# PitchshiftDelay-Control-v1_2.net
KiCad netlist of a schematic drawn in EAGLE
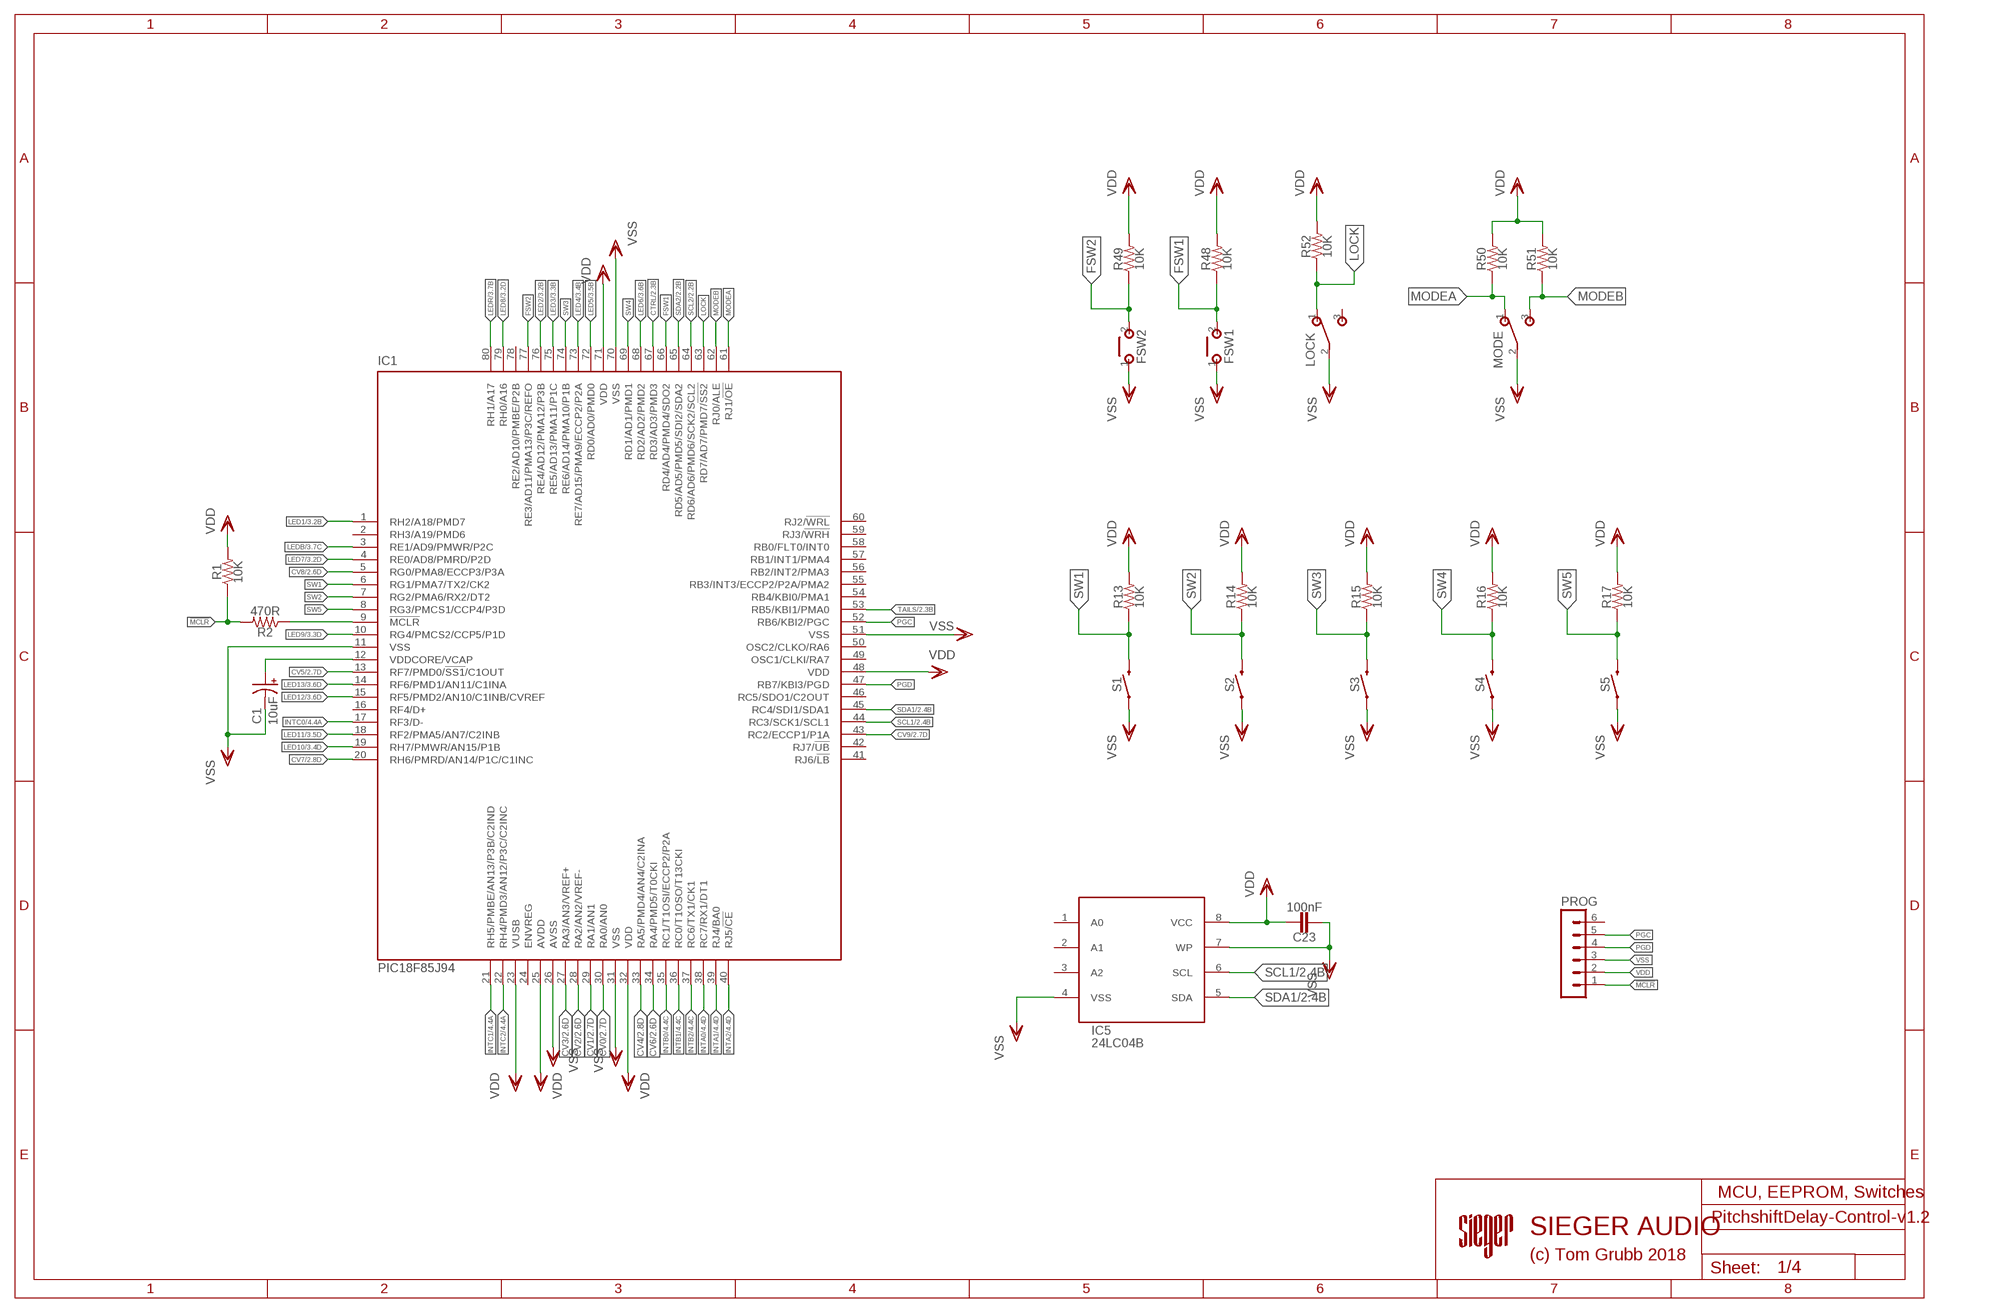
[diagram p0: schematic, sheet 1]
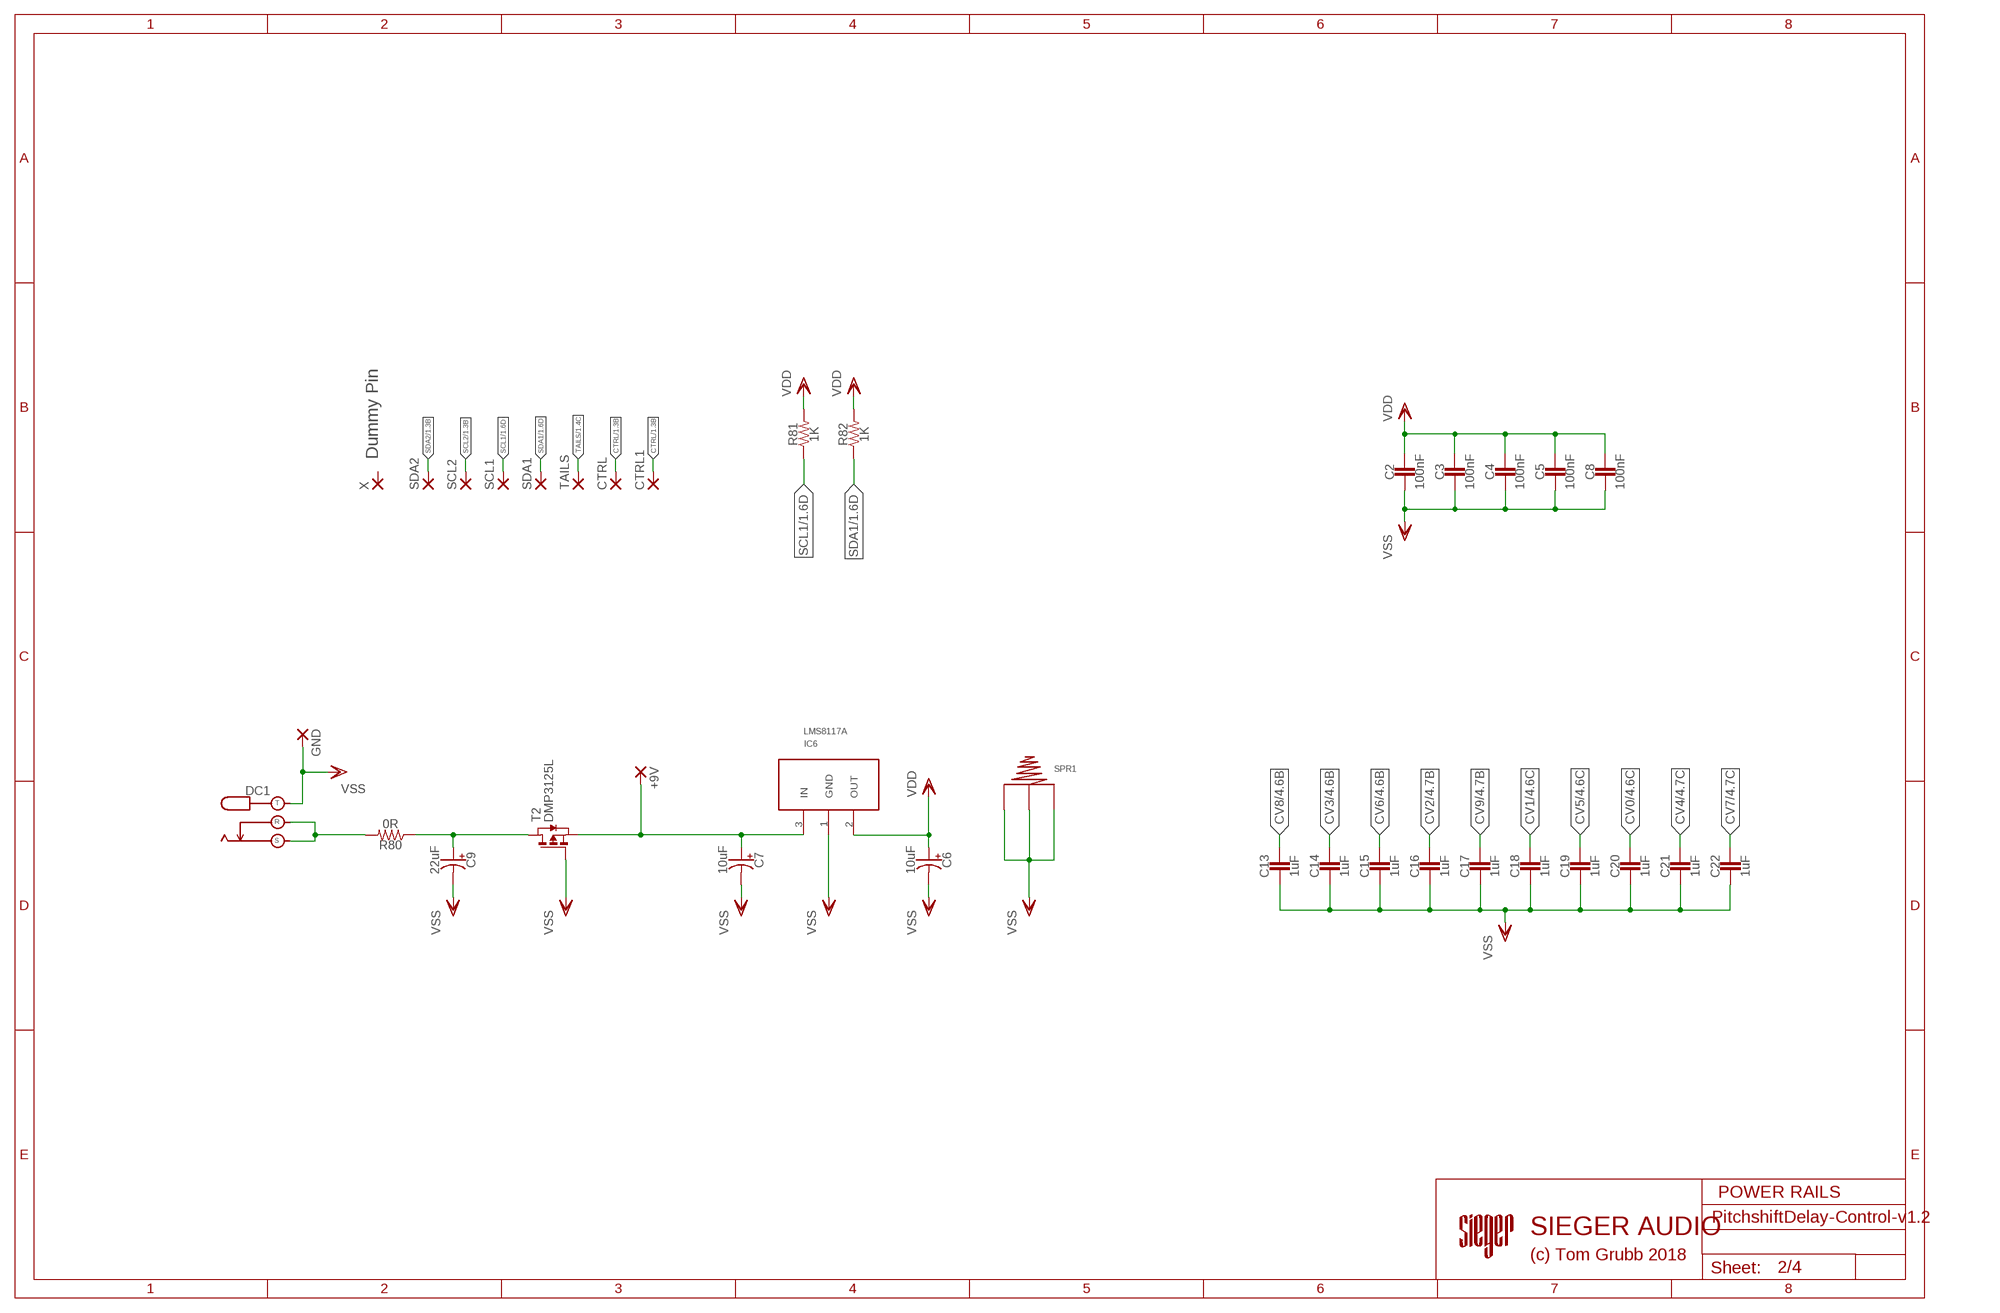
[diagram p1: schematic, sheet 2]
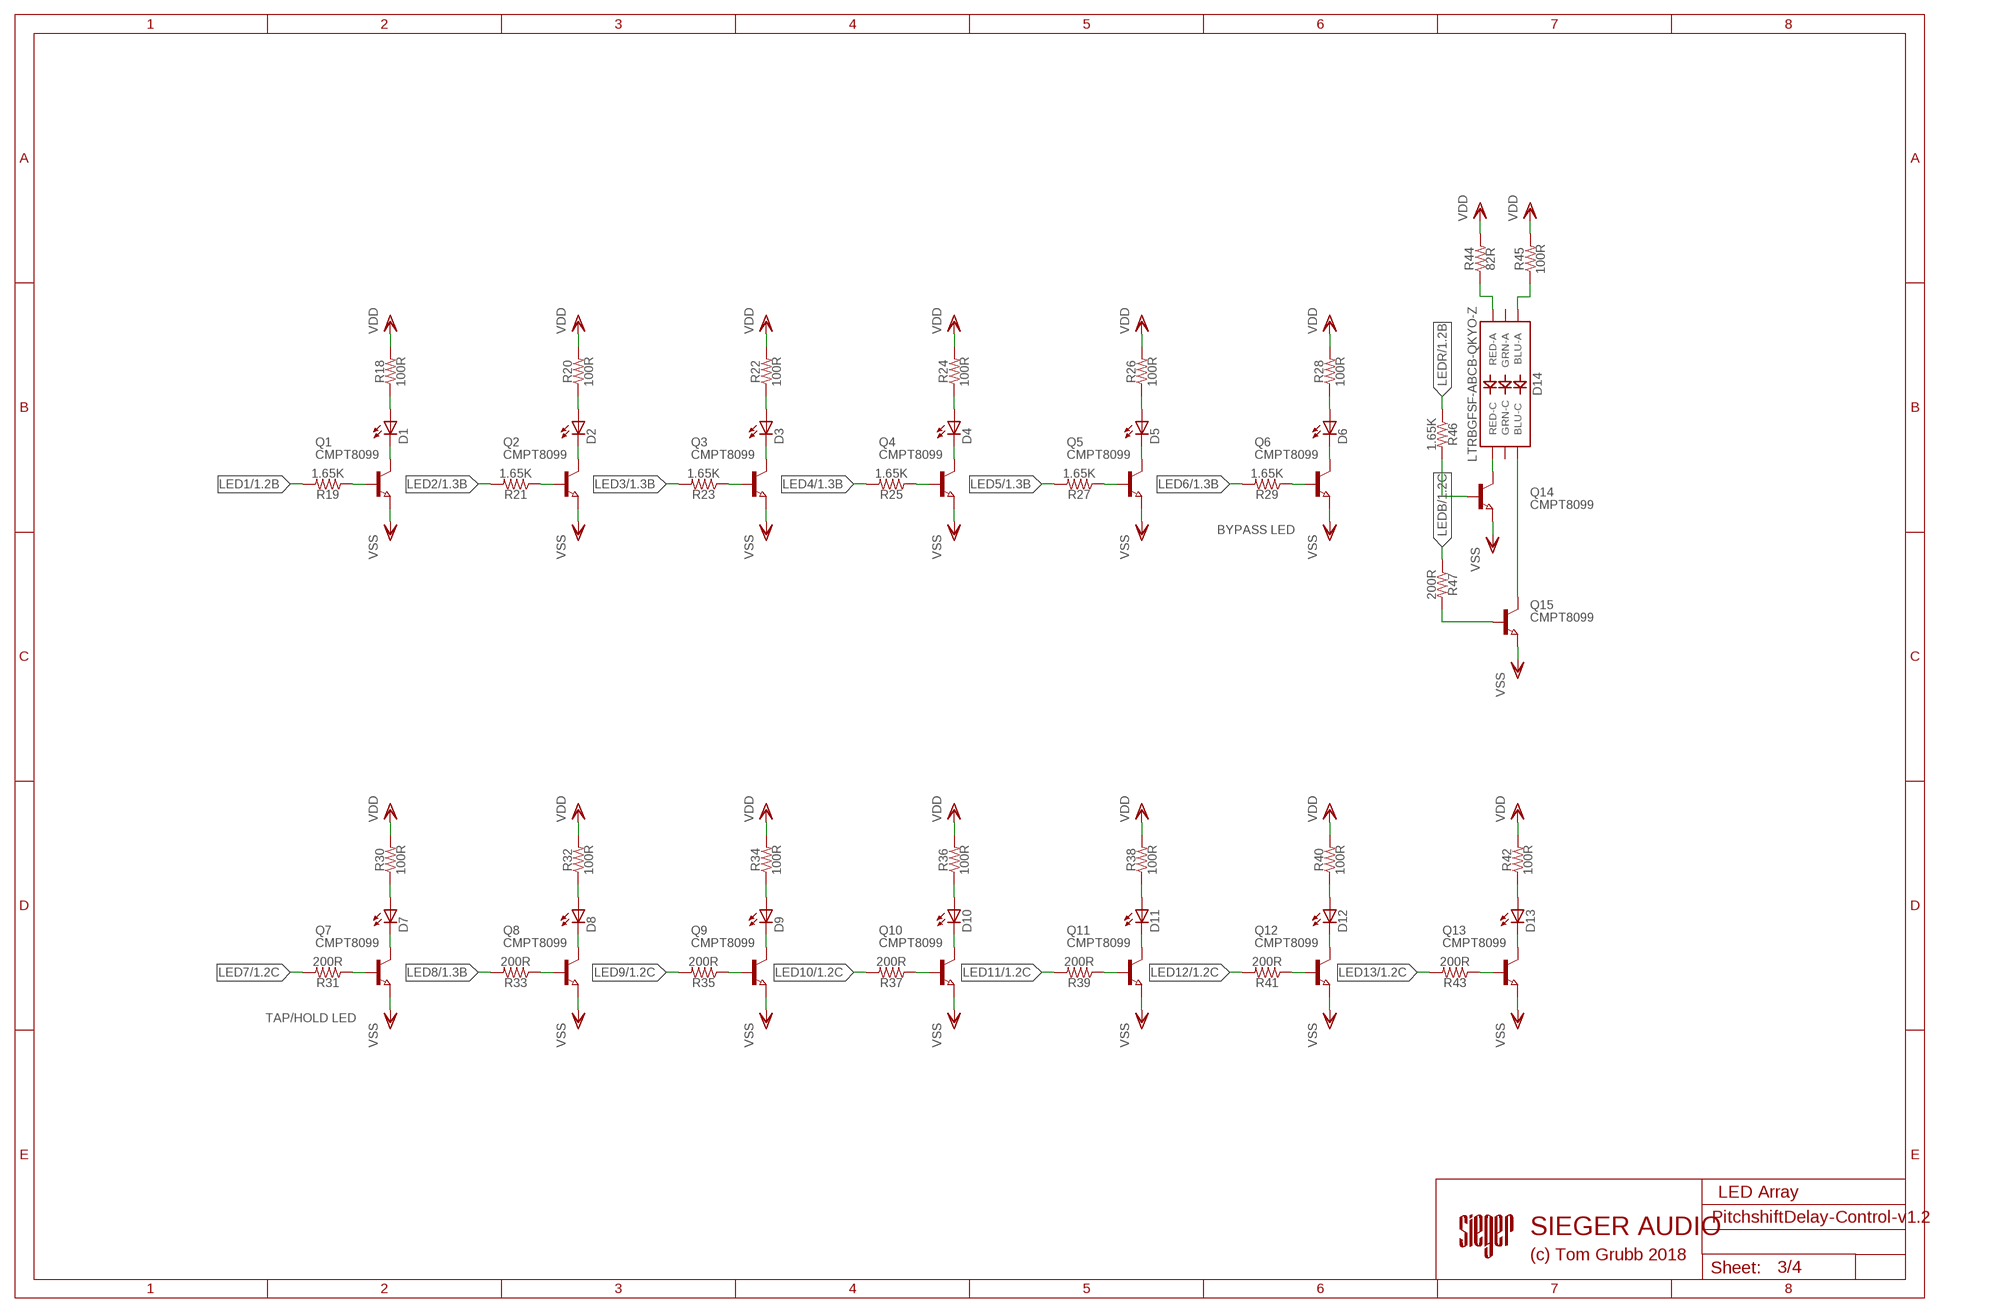
[diagram p2: schematic, sheet 3]
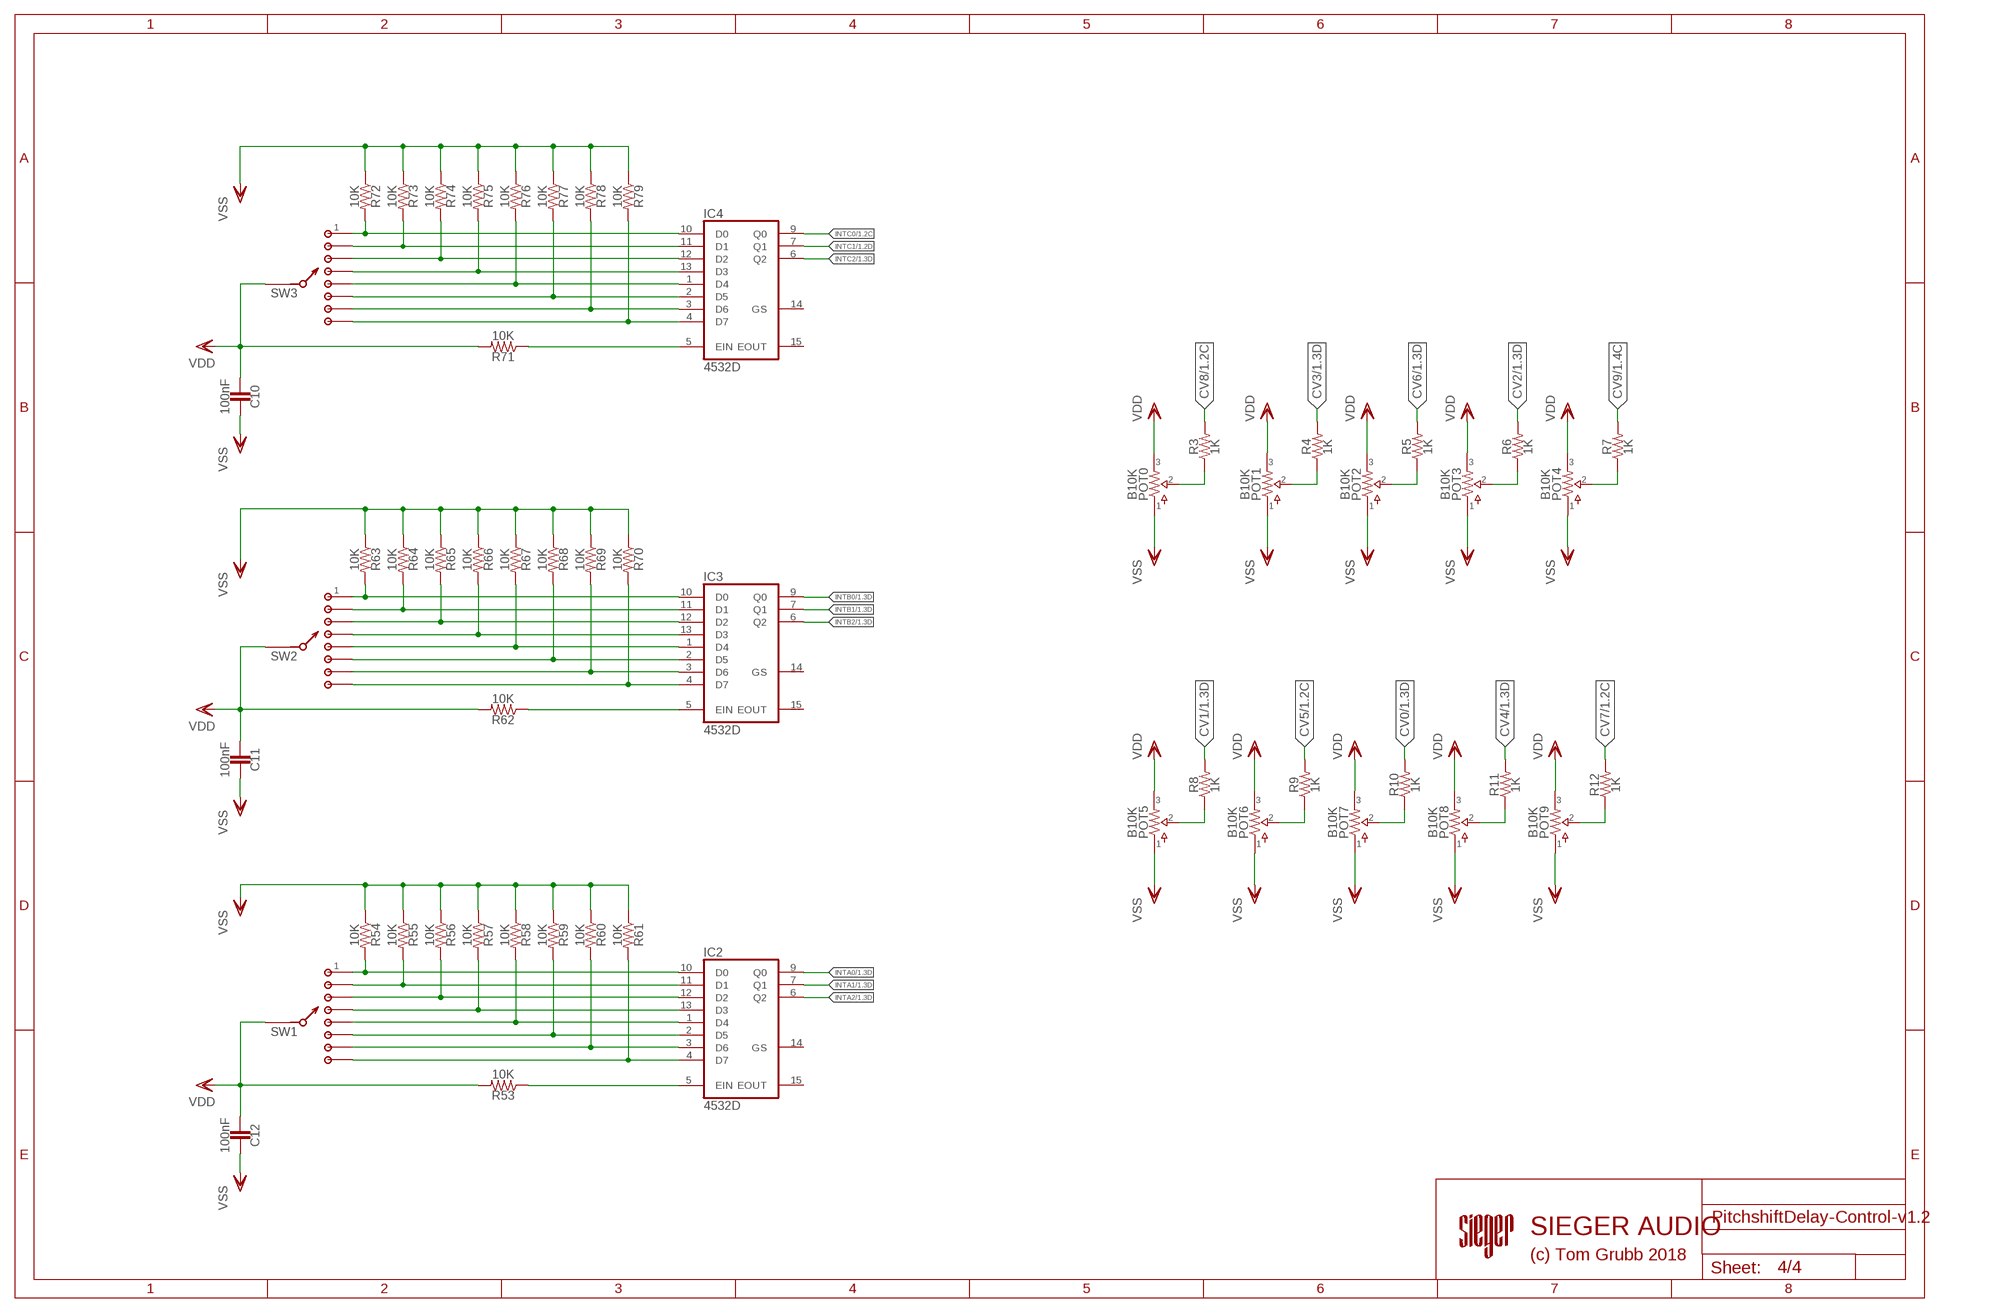
[diagram p3: schematic, sheet 4]

(export (version "E")
  (design (tool "Eeschema 10.0.6"))
  (components
    (comp (ref "C10")
      (value "100nF")
      (footprint "eagle-import:050X030_025")
      (libsource (lib "eagle-import") (part "CER/FILM1"))
    )
    (comp (ref "C11")
      (value "100nF")
      (footprint "eagle-import:050X030_025")
      (libsource (lib "eagle-import") (part "CER/FILM1"))
    )
    (comp (ref "C12")
      (value "100nF")
      (footprint "eagle-import:050X030_025")
      (libsource (lib "eagle-import") (part "CER/FILM1"))
    )
    (comp (ref "IC2")
      (value "4532D")
      (footprint "eagle-import:SO16")
      (libsource (lib "eagle-import") (part "4532D"))
    )
    (comp (ref "IC3")
      (value "4532D")
      (footprint "eagle-import:SO16")
      (libsource (lib "eagle-import") (part "4532D"))
    )
    (comp (ref "IC4")
      (value "4532D")
      (footprint "eagle-import:SO16")
      (libsource (lib "eagle-import") (part "4532D"))
    )
    (comp (ref "POT0")
      (value "B10K")
      (footprint "eagle-import:9MM_W_MOUNTS-2MMHOLES")
      (libsource (lib "eagle-import") (part "POTS9MM_MOUNTED_2MMH"))
    )
    (comp (ref "POT1")
      (value "B10K")
      (footprint "eagle-import:9MM_W_MOUNTS-2MMHOLES")
      (libsource (lib "eagle-import") (part "POTS9MM_MOUNTED_2MMH"))
    )
    (comp (ref "POT2")
      (value "B10K")
      (footprint "eagle-import:9MM_W_MOUNTS-2MMHOLES")
      (libsource (lib "eagle-import") (part "POTS9MM_MOUNTED_2MMH"))
    )
    (comp (ref "POT3")
      (value "B10K")
      (footprint "eagle-import:9MM_W_MOUNTS-2MMHOLES")
      (libsource (lib "eagle-import") (part "POTS9MM_MOUNTED_2MMH"))
    )
    (comp (ref "POT4")
      (value "B10K")
      (footprint "eagle-import:9MM_W_MOUNTS-2MMHOLES")
      (libsource (lib "eagle-import") (part "POTS9MM_MOUNTED_2MMH"))
    )
    (comp (ref "POT5")
      (value "B10K")
      (footprint "eagle-import:9MM_W_MOUNTS-2MMHOLES")
      (libsource (lib "eagle-import") (part "POTS9MM_MOUNTED_2MMH"))
    )
    (comp (ref "POT6")
      (value "B10K")
      (footprint "eagle-import:9MM_W_MOUNTS-2MMHOLES")
      (libsource (lib "eagle-import") (part "POTS9MM_MOUNTED_2MMH"))
    )
    (comp (ref "POT7")
      (value "B10K")
      (footprint "eagle-import:9MM_W_MOUNTS-2MMHOLES")
      (libsource (lib "eagle-import") (part "POTS9MM_MOUNTED_2MMH"))
    )
    (comp (ref "POT8")
      (value "B10K")
      (footprint "eagle-import:9MM_W_MOUNTS-2MMHOLES")
      (libsource (lib "eagle-import") (part "POTS9MM_MOUNTED_2MMH"))
    )
    (comp (ref "POT9")
      (value "B10K")
      (footprint "eagle-import:9MM_W_MOUNTS-2MMHOLES")
      (libsource (lib "eagle-import") (part "POTS9MM_MOUNTED_2MMH"))
    )
    (comp (ref "R3")
      (value "1K")
      (footprint "eagle-import:RESISTOR_C0805")
      (libsource (lib "eagle-import") (part "RESISTOR0805"))
    )
    (comp (ref "R4")
      (value "1K")
      (footprint "eagle-import:RESISTOR_C0805")
      (libsource (lib "eagle-import") (part "RESISTOR0805"))
    )
    (comp (ref "R5")
      (value "1K")
      (footprint "eagle-import:RESISTOR_C0805")
      (libsource (lib "eagle-import") (part "RESISTOR0805"))
    )
    (comp (ref "R6")
      (value "1K")
      (footprint "eagle-import:RESISTOR_C0805")
      (libsource (lib "eagle-import") (part "RESISTOR0805"))
    )
    (comp (ref "R7")
      (value "1K")
      (footprint "eagle-import:RESISTOR_C0805")
      (libsource (lib "eagle-import") (part "RESISTOR0805"))
    )
    (comp (ref "R8")
      (value "1K")
      (footprint "eagle-import:RESISTOR_C0805")
      (libsource (lib "eagle-import") (part "RESISTOR0805"))
    )
    (comp (ref "R9")
      (value "1K")
      (footprint "eagle-import:RESISTOR_C0805")
      (libsource (lib "eagle-import") (part "RESISTOR0805"))
    )
    (comp (ref "R10")
      (value "1K")
      (footprint "eagle-import:RESISTOR_C0805")
      (libsource (lib "eagle-import") (part "RESISTOR0805"))
    )
    (comp (ref "R11")
      (value "1K")
      (footprint "eagle-import:RESISTOR_C0805")
      (libsource (lib "eagle-import") (part "RESISTOR0805"))
    )
    (comp (ref "R12")
      (value "1K")
      (footprint "eagle-import:RESISTOR_C0805")
      (libsource (lib "eagle-import") (part "RESISTOR0805"))
    )
    (comp (ref "R53")
      (value "10K")
      (footprint "eagle-import:RESISTOR_C0805")
      (fields (field (name "SPICEPREFIX") "R"))
      (libsource (lib "eagle-import") (part "RESISTOR0805"))
    )
    (comp (ref "R54")
      (value "10K")
      (footprint "eagle-import:RESISTOR_C0805")
      (fields (field (name "SPICEPREFIX") "R"))
      (libsource (lib "eagle-import") (part "RESISTOR0805"))
    )
    (comp (ref "R55")
      (value "10K")
      (footprint "eagle-import:RESISTOR_C0805")
      (fields (field (name "SPICEPREFIX") "R"))
      (libsource (lib "eagle-import") (part "RESISTOR0805"))
    )
    (comp (ref "R56")
      (value "10K")
      (footprint "eagle-import:RESISTOR_C0805")
      (fields (field (name "SPICEPREFIX") "R"))
      (libsource (lib "eagle-import") (part "RESISTOR0805"))
    )
    (comp (ref "R57")
      (value "10K")
      (footprint "eagle-import:RESISTOR_C0805")
      (fields (field (name "SPICEPREFIX") "R"))
      (libsource (lib "eagle-import") (part "RESISTOR0805"))
    )
    (comp (ref "R58")
      (value "10K")
      (footprint "eagle-import:RESISTOR_C0805")
      (fields (field (name "SPICEPREFIX") "R"))
      (libsource (lib "eagle-import") (part "RESISTOR0805"))
    )
    (comp (ref "R59")
      (value "10K")
      (footprint "eagle-import:RESISTOR_C0805")
      (fields (field (name "SPICEPREFIX") "R"))
      (libsource (lib "eagle-import") (part "RESISTOR0805"))
    )
    (comp (ref "R60")
      (value "10K")
      (footprint "eagle-import:RESISTOR_C0805")
      (fields (field (name "SPICEPREFIX") "R"))
      (libsource (lib "eagle-import") (part "RESISTOR0805"))
    )
    (comp (ref "R61")
      (value "10K")
      (footprint "eagle-import:RESISTOR_C0805")
      (fields (field (name "SPICEPREFIX") "R"))
      (libsource (lib "eagle-import") (part "RESISTOR0805"))
    )
    (comp (ref "R62")
      (value "10K")
      (footprint "eagle-import:RESISTOR_C0805")
      (fields (field (name "SPICEPREFIX") "R"))
      (libsource (lib "eagle-import") (part "RESISTOR0805"))
    )
    (comp (ref "R63")
      (value "10K")
      (footprint "eagle-import:RESISTOR_C0805")
      (fields (field (name "SPICEPREFIX") "R"))
      (libsource (lib "eagle-import") (part "RESISTOR0805"))
    )
    (comp (ref "R64")
      (value "10K")
      (footprint "eagle-import:RESISTOR_C0805")
      (fields (field (name "SPICEPREFIX") "R"))
      (libsource (lib "eagle-import") (part "RESISTOR0805"))
    )
    (comp (ref "R65")
      (value "10K")
      (footprint "eagle-import:RESISTOR_C0805")
      (fields (field (name "SPICEPREFIX") "R"))
      (libsource (lib "eagle-import") (part "RESISTOR0805"))
    )
    (comp (ref "R66")
      (value "10K")
      (footprint "eagle-import:RESISTOR_C0805")
      (fields (field (name "SPICEPREFIX") "R"))
      (libsource (lib "eagle-import") (part "RESISTOR0805"))
    )
    (comp (ref "R67")
      (value "10K")
      (footprint "eagle-import:RESISTOR_C0805")
      (fields (field (name "SPICEPREFIX") "R"))
      (libsource (lib "eagle-import") (part "RESISTOR0805"))
    )
    (comp (ref "R68")
      (value "10K")
      (footprint "eagle-import:RESISTOR_C0805")
      (fields (field (name "SPICEPREFIX") "R"))
      (libsource (lib "eagle-import") (part "RESISTOR0805"))
    )
    (comp (ref "R69")
      (value "10K")
      (footprint "eagle-import:RESISTOR_C0805")
      (fields (field (name "SPICEPREFIX") "R"))
      (libsource (lib "eagle-import") (part "RESISTOR0805"))
    )
    (comp (ref "R70")
      (value "10K")
      (footprint "eagle-import:RESISTOR_C0805")
      (fields (field (name "SPICEPREFIX") "R"))
      (libsource (lib "eagle-import") (part "RESISTOR0805"))
    )
    (comp (ref "R71")
      (value "10K")
      (footprint "eagle-import:RESISTOR_C0805")
      (fields (field (name "SPICEPREFIX") "R"))
      (libsource (lib "eagle-import") (part "RESISTOR0805"))
    )
    (comp (ref "R72")
      (value "10K")
      (footprint "eagle-import:RESISTOR_C0805")
      (fields (field (name "SPICEPREFIX") "R"))
      (libsource (lib "eagle-import") (part "RESISTOR0805"))
    )
    (comp (ref "R73")
      (value "10K")
      (footprint "eagle-import:RESISTOR_C0805")
      (fields (field (name "SPICEPREFIX") "R"))
      (libsource (lib "eagle-import") (part "RESISTOR0805"))
    )
    (comp (ref "R74")
      (value "10K")
      (footprint "eagle-import:RESISTOR_C0805")
      (fields (field (name "SPICEPREFIX") "R"))
      (libsource (lib "eagle-import") (part "RESISTOR0805"))
    )
    (comp (ref "R75")
      (value "10K")
      (footprint "eagle-import:RESISTOR_C0805")
      (fields (field (name "SPICEPREFIX") "R"))
      (libsource (lib "eagle-import") (part "RESISTOR0805"))
    )
    (comp (ref "R76")
      (value "10K")
      (footprint "eagle-import:RESISTOR_C0805")
      (fields (field (name "SPICEPREFIX") "R"))
      (libsource (lib "eagle-import") (part "RESISTOR0805"))
    )
    (comp (ref "R77")
      (value "10K")
      (footprint "eagle-import:RESISTOR_C0805")
      (fields (field (name "SPICEPREFIX") "R"))
      (libsource (lib "eagle-import") (part "RESISTOR0805"))
    )
    (comp (ref "R78")
      (value "10K")
      (footprint "eagle-import:RESISTOR_C0805")
      (fields (field (name "SPICEPREFIX") "R"))
      (libsource (lib "eagle-import") (part "RESISTOR0805"))
    )
    (comp (ref "R79")
      (value "10K")
      (footprint "eagle-import:RESISTOR_C0805")
      (fields (field (name "SPICEPREFIX") "R"))
      (libsource (lib "eagle-import") (part "RESISTOR0805"))
    )
    (comp (ref "SW1")
      (value "1P8T")
      (footprint "eagle-import:SMALLROTARY")
      (libsource (lib "eagle-import") (part "1P8T"))
    )
    (comp (ref "SW2")
      (value "1P8T")
      (footprint "eagle-import:SMALLROTARY")
      (libsource (lib "eagle-import") (part "1P8T"))
    )
    (comp (ref "SW3")
      (value "1P8T")
      (footprint "eagle-import:SMALLROTARY")
      (libsource (lib "eagle-import") (part "1P8T"))
    )
    (comp (ref "+9V")
      (value "2,15/1,0")
      (footprint "eagle-import:2,15_1,0")
      (libsource (lib "eagle-import") (part "2,15/1,0"))
    )
    (comp (ref "C2")
      (value "100nF")
      (footprint "eagle-import:050X030_025")
      (libsource (lib "eagle-import") (part "CER/FILM1"))
    )
    (comp (ref "C3")
      (value "100nF")
      (footprint "eagle-import:050X030_025")
      (libsource (lib "eagle-import") (part "CER/FILM1"))
    )
    (comp (ref "C4")
      (value "100nF")
      (footprint "eagle-import:050X030_025")
      (libsource (lib "eagle-import") (part "CER/FILM1"))
    )
    (comp (ref "C5")
      (value "100nF")
      (footprint "eagle-import:050X030_025")
      (libsource (lib "eagle-import") (part "CER/FILM1"))
    )
    (comp (ref "C6")
      (value "10uF")
      (footprint "eagle-import:050_020_1")
      (libsource (lib "eagle-import") (part "0501"))
    )
    (comp (ref "C7")
      (value "10uF")
      (footprint "eagle-import:050_020_1")
      (libsource (lib "eagle-import") (part "0501"))
    )
    (comp (ref "C8")
      (value "100nF")
      (footprint "eagle-import:050X030_025")
      (libsource (lib "eagle-import") (part "CER/FILM1"))
    )
    (comp (ref "C9")
      (value "22uF")
      (footprint "eagle-import:050_020_1")
      (libsource (lib "eagle-import") (part "0501"))
    )
    (comp (ref "C13")
      (value "1uF")
      (footprint "eagle-import:050X030_025")
      (libsource (lib "eagle-import") (part "CER/FILM1"))
    )
    (comp (ref "C14")
      (value "1uF")
      (footprint "eagle-import:050X030_025")
      (libsource (lib "eagle-import") (part "CER/FILM1"))
    )
    (comp (ref "C15")
      (value "1uF")
      (footprint "eagle-import:050X030_025")
      (libsource (lib "eagle-import") (part "CER/FILM1"))
    )
    (comp (ref "C16")
      (value "1uF")
      (footprint "eagle-import:050X030_025")
      (libsource (lib "eagle-import") (part "CER/FILM1"))
    )
    (comp (ref "C17")
      (value "1uF")
      (footprint "eagle-import:050X030_025")
      (libsource (lib "eagle-import") (part "CER/FILM1"))
    )
    (comp (ref "C18")
      (value "1uF")
      (footprint "eagle-import:050X030_025")
      (libsource (lib "eagle-import") (part "CER/FILM1"))
    )
    (comp (ref "C19")
      (value "1uF")
      (footprint "eagle-import:050X030_025")
      (libsource (lib "eagle-import") (part "CER/FILM1"))
    )
    (comp (ref "C20")
      (value "1uF")
      (footprint "eagle-import:050X030_025")
      (libsource (lib "eagle-import") (part "CER/FILM1"))
    )
    (comp (ref "C21")
      (value "1uF")
      (footprint "eagle-import:050X030_025")
      (libsource (lib "eagle-import") (part "CER/FILM1"))
    )
    (comp (ref "C22")
      (value "1uF")
      (footprint "eagle-import:050X030_025")
      (libsource (lib "eagle-import") (part "CER/FILM1"))
    )
    (comp (ref "CTRL")
      (value "2,15/1,0")
      (footprint "eagle-import:2,15_1,0")
      (libsource (lib "eagle-import") (part "2,15/1,0"))
    )
    (comp (ref "CTRL1")
      (value "2,15/1,0")
      (footprint "eagle-import:2,15_1,0")
      (libsource (lib "eagle-import") (part "2,15/1,0"))
    )
    (comp (ref "DC1")
      (value "DC_KOBICONN")
      (footprint "eagle-import:DC_KOBICONN")
      (libsource (lib "eagle-import") (part "DC_KOBICONN"))
    )
    (comp (ref "GND")
      (value "2,15/1,0")
      (footprint "eagle-import:2,15_1,0")
      (libsource (lib "eagle-import") (part "2,15/1,0"))
    )
    (comp (ref "IC6")
      (value "LMS8117A")
      (footprint "eagle-import:SOT223")
      (libsource (lib "eagle-import") (part "LMS8117A"))
    )
    (comp (ref "R80")
      (value "0R")
      (footprint "eagle-import:RESISTOR_C0805")
      (libsource (lib "eagle-import") (part "RESISTOR0805"))
    )
    (comp (ref "R81")
      (value "1K")
      (footprint "eagle-import:RESISTOR_C0805")
      (libsource (lib "eagle-import") (part "RESISTOR0805"))
    )
    (comp (ref "R82")
      (value "1K")
      (footprint "eagle-import:RESISTOR_C0805")
      (libsource (lib "eagle-import") (part "RESISTOR0805"))
    )
    (comp (ref "SCL1")
      (value "2,15/1,0")
      (footprint "eagle-import:2,15_1,0")
      (libsource (lib "eagle-import") (part "2,15/1,0"))
    )
    (comp (ref "SCL2")
      (value "2,15/1,0")
      (footprint "eagle-import:2,15_1,0")
      (libsource (lib "eagle-import") (part "2,15/1,0"))
    )
    (comp (ref "SDA1")
      (value "2,15/1,0")
      (footprint "eagle-import:2,15_1,0")
      (libsource (lib "eagle-import") (part "2,15/1,0"))
    )
    (comp (ref "SDA2")
      (value "2,15/1,0")
      (footprint "eagle-import:2,15_1,0")
      (libsource (lib "eagle-import") (part "2,15/1,0"))
    )
    (comp (ref "SPR1")
      (value "534-628")
      (footprint "eagle-import:'A'SIZE-PC-SPRING")
      (libsource (lib "eagle-import") (part "SPRING"))
    )
    (comp (ref "T2")
      (value "DMP3125L")
      (footprint "eagle-import:SOT-23")
      (libsource (lib "eagle-import") (part "PMOSSOT23"))
    )
    (comp (ref "TAILS")
      (value "2,15/1,0")
      (footprint "eagle-import:2,15_1,0")
      (libsource (lib "eagle-import") (part "2,15/1,0"))
    )
    (comp (ref "X")
      (value "2,15/1,0")
      (footprint "eagle-import:2,15_1,0")
      (libsource (lib "eagle-import") (part "2,15/1,0"))
    )
    (comp (ref "D1")
      (value "LEDCHIP-LED0805")
      (footprint "eagle-import:CHIP-LED0805")
      (libsource (lib "eagle-import") (part "LEDCHIP-LED0805"))
    )
    (comp (ref "D2")
      (value "LEDCHIP-LED0805")
      (footprint "eagle-import:CHIP-LED0805")
      (libsource (lib "eagle-import") (part "LEDCHIP-LED0805"))
    )
    (comp (ref "D3")
      (value "LEDCHIP-LED0805")
      (footprint "eagle-import:CHIP-LED0805")
      (libsource (lib "eagle-import") (part "LEDCHIP-LED0805"))
    )
    (comp (ref "D4")
      (value "LEDCHIP-LED0805")
      (footprint "eagle-import:CHIP-LED0805")
      (libsource (lib "eagle-import") (part "LEDCHIP-LED0805"))
    )
    (comp (ref "D5")
      (value "LEDCHIP-LED0805")
      (footprint "eagle-import:CHIP-LED0805")
      (libsource (lib "eagle-import") (part "LEDCHIP-LED0805"))
    )
    (comp (ref "D6")
      (value "LEDCHIPLED_1206")
      (footprint "eagle-import:CHIPLED_1206")
      (libsource (lib "eagle-import") (part "LEDCHIPLED_1206"))
    )
    (comp (ref "D7")
      (value "LEDCHIPLED_1206")
      (footprint "eagle-import:CHIPLED_1206")
      (libsource (lib "eagle-import") (part "LEDCHIPLED_1206"))
    )
    (comp (ref "D8")
      (value "LEDCHIP-LED0805")
      (footprint "eagle-import:CHIP-LED0805")
      (libsource (lib "eagle-import") (part "LEDCHIP-LED0805"))
    )
    (comp (ref "D9")
      (value "LEDCHIP-LED0805")
      (footprint "eagle-import:CHIP-LED0805")
      (libsource (lib "eagle-import") (part "LEDCHIP-LED0805"))
    )
    (comp (ref "D10")
      (value "LEDCHIP-LED0805")
      (footprint "eagle-import:CHIP-LED0805")
      (libsource (lib "eagle-import") (part "LEDCHIP-LED0805"))
    )
    (comp (ref "D11")
      (value "LEDCHIP-LED0805")
      (footprint "eagle-import:CHIP-LED0805")
      (libsource (lib "eagle-import") (part "LEDCHIP-LED0805"))
    )
    (comp (ref "D12")
      (value "LEDCHIP-LED0805")
      (footprint "eagle-import:CHIP-LED0805")
      (libsource (lib "eagle-import") (part "LEDCHIP-LED0805"))
    )
    (comp (ref "D13")
      (value "LEDCHIP-LED0805")
      (footprint "eagle-import:CHIP-LED0805")
      (libsource (lib "eagle-import") (part "LEDCHIP-LED0805"))
    )
    (comp (ref "D14")
      (value "LTRBGFSF-ABCB-QKYO-Z")
      (footprint "eagle-import:PLCC-6-LED")
      (libsource (lib "eagle-import") (part "LED-RGBPLCC-6"))
    )
    (comp (ref "Q1")
      (value "CMPT8099")
      (footprint "eagle-import:SOT23")
      (libsource (lib "eagle-import") (part "NPN-TRANSISTOR_SOT23"))
    )
    (comp (ref "Q2")
      (value "CMPT8099")
      (footprint "eagle-import:SOT23")
      (libsource (lib "eagle-import") (part "NPN-TRANSISTOR_SOT23"))
    )
    (comp (ref "Q3")
      (value "CMPT8099")
      (footprint "eagle-import:SOT23")
      (libsource (lib "eagle-import") (part "NPN-TRANSISTOR_SOT23"))
    )
    (comp (ref "Q4")
      (value "CMPT8099")
      (footprint "eagle-import:SOT23")
      (libsource (lib "eagle-import") (part "NPN-TRANSISTOR_SOT23"))
    )
    (comp (ref "Q5")
      (value "CMPT8099")
      (footprint "eagle-import:SOT23")
      (libsource (lib "eagle-import") (part "NPN-TRANSISTOR_SOT23"))
    )
    (comp (ref "Q6")
      (value "CMPT8099")
      (footprint "eagle-import:SOT23")
      (libsource (lib "eagle-import") (part "NPN-TRANSISTOR_SOT23"))
    )
    (comp (ref "Q7")
      (value "CMPT8099")
      (footprint "eagle-import:SOT23")
      (libsource (lib "eagle-import") (part "NPN-TRANSISTOR_SOT23"))
    )
    (comp (ref "Q8")
      (value "CMPT8099")
      (footprint "eagle-import:SOT23")
      (libsource (lib "eagle-import") (part "NPN-TRANSISTOR_SOT23"))
    )
    (comp (ref "Q9")
      (value "CMPT8099")
      (footprint "eagle-import:SOT23")
      (libsource (lib "eagle-import") (part "NPN-TRANSISTOR_SOT23"))
    )
    (comp (ref "Q10")
      (value "CMPT8099")
      (footprint "eagle-import:SOT23")
      (libsource (lib "eagle-import") (part "NPN-TRANSISTOR_SOT23"))
    )
    (comp (ref "Q11")
      (value "CMPT8099")
      (footprint "eagle-import:SOT23")
      (libsource (lib "eagle-import") (part "NPN-TRANSISTOR_SOT23"))
    )
    (comp (ref "Q12")
      (value "CMPT8099")
      (footprint "eagle-import:SOT23")
      (libsource (lib "eagle-import") (part "NPN-TRANSISTOR_SOT23"))
    )
    (comp (ref "Q13")
      (value "CMPT8099")
      (footprint "eagle-import:SOT23")
      (libsource (lib "eagle-import") (part "NPN-TRANSISTOR_SOT23"))
    )
    (comp (ref "Q14")
      (value "CMPT8099")
      (footprint "eagle-import:SOT23")
      (libsource (lib "eagle-import") (part "NPN-TRANSISTOR_SOT23"))
    )
    (comp (ref "Q15")
      (value "CMPT8099")
      (footprint "eagle-import:SOT23")
      (libsource (lib "eagle-import") (part "NPN-TRANSISTOR_SOT23"))
    )
    (comp (ref "R18")
      (value "100R")
      (footprint "eagle-import:RESISTOR_C0805")
      (libsource (lib "eagle-import") (part "RESISTOR0805"))
    )
    (comp (ref "R19")
      (value "1.65K")
      (footprint "eagle-import:RESISTOR_C0805")
      (libsource (lib "eagle-import") (part "RESISTOR0805"))
    )
    (comp (ref "R20")
      (value "100R")
      (footprint "eagle-import:RESISTOR_C0805")
      (libsource (lib "eagle-import") (part "RESISTOR0805"))
    )
    (comp (ref "R21")
      (value "1.65K")
      (footprint "eagle-import:RESISTOR_C0805")
      (libsource (lib "eagle-import") (part "RESISTOR0805"))
    )
    (comp (ref "R22")
      (value "100R")
      (footprint "eagle-import:RESISTOR_C0805")
      (libsource (lib "eagle-import") (part "RESISTOR0805"))
    )
    (comp (ref "R23")
      (value "1.65K")
      (footprint "eagle-import:RESISTOR_C0805")
      (libsource (lib "eagle-import") (part "RESISTOR0805"))
    )
    (comp (ref "R24")
      (value "100R")
      (footprint "eagle-import:RESISTOR_C0805")
      (libsource (lib "eagle-import") (part "RESISTOR0805"))
    )
    (comp (ref "R25")
      (value "1.65K")
      (footprint "eagle-import:RESISTOR_C0805")
      (libsource (lib "eagle-import") (part "RESISTOR0805"))
    )
    (comp (ref "R26")
      (value "100R")
      (footprint "eagle-import:RESISTOR_C0805")
      (libsource (lib "eagle-import") (part "RESISTOR0805"))
    )
    (comp (ref "R27")
      (value "1.65K")
      (footprint "eagle-import:RESISTOR_C0805")
      (libsource (lib "eagle-import") (part "RESISTOR0805"))
    )
    (comp (ref "R28")
      (value "100R")
      (footprint "eagle-import:RESISTOR_C0805")
      (libsource (lib "eagle-import") (part "RESISTOR0805"))
    )
    (comp (ref "R29")
      (value "1.65K")
      (footprint "eagle-import:RESISTOR_C0805")
      (libsource (lib "eagle-import") (part "RESISTOR0805"))
    )
    (comp (ref "R30")
      (value "100R")
      (footprint "eagle-import:RESISTOR_C0805")
      (libsource (lib "eagle-import") (part "RESISTOR0805"))
    )
    (comp (ref "R31")
      (value "200R")
      (footprint "eagle-import:RESISTOR_C0805")
      (libsource (lib "eagle-import") (part "RESISTOR0805"))
    )
    (comp (ref "R32")
      (value "100R")
      (footprint "eagle-import:RESISTOR_C0805")
      (libsource (lib "eagle-import") (part "RESISTOR0805"))
    )
    (comp (ref "R33")
      (value "200R")
      (footprint "eagle-import:RESISTOR_C0805")
      (libsource (lib "eagle-import") (part "RESISTOR0805"))
    )
    (comp (ref "R34")
      (value "100R")
      (footprint "eagle-import:RESISTOR_C0805")
      (libsource (lib "eagle-import") (part "RESISTOR0805"))
    )
    (comp (ref "R35")
      (value "200R")
      (footprint "eagle-import:RESISTOR_C0805")
      (libsource (lib "eagle-import") (part "RESISTOR0805"))
    )
    (comp (ref "R36")
      (value "100R")
      (footprint "eagle-import:RESISTOR_C0805")
      (libsource (lib "eagle-import") (part "RESISTOR0805"))
    )
    (comp (ref "R37")
      (value "200R")
      (footprint "eagle-import:RESISTOR_C0805")
      (libsource (lib "eagle-import") (part "RESISTOR0805"))
    )
    (comp (ref "R38")
      (value "100R")
      (footprint "eagle-import:RESISTOR_C0805")
      (libsource (lib "eagle-import") (part "RESISTOR0805"))
    )
    (comp (ref "R39")
      (value "200R")
      (footprint "eagle-import:RESISTOR_C0805")
      (libsource (lib "eagle-import") (part "RESISTOR0805"))
    )
    (comp (ref "R40")
      (value "100R")
      (footprint "eagle-import:RESISTOR_C0805")
      (libsource (lib "eagle-import") (part "RESISTOR0805"))
    )
    (comp (ref "R41")
      (value "200R")
      (footprint "eagle-import:RESISTOR_C0805")
      (libsource (lib "eagle-import") (part "RESISTOR0805"))
    )
    (comp (ref "R42")
      (value "100R")
      (footprint "eagle-import:RESISTOR_C0805")
      (libsource (lib "eagle-import") (part "RESISTOR0805"))
    )
    (comp (ref "R43")
      (value "200R")
      (footprint "eagle-import:RESISTOR_C0805")
      (libsource (lib "eagle-import") (part "RESISTOR0805"))
    )
    (comp (ref "R44")
      (value "82R")
      (footprint "eagle-import:RESISTOR_C0805")
      (libsource (lib "eagle-import") (part "RESISTOR0805"))
    )
    (comp (ref "R45")
      (value "100R")
      (footprint "eagle-import:RESISTOR_C0805")
      (libsource (lib "eagle-import") (part "RESISTOR0805"))
    )
    (comp (ref "R46")
      (value "1.65K")
      (footprint "eagle-import:RESISTOR_C0805")
      (libsource (lib "eagle-import") (part "RESISTOR0805"))
    )
    (comp (ref "R47")
      (value "200R")
      (footprint "eagle-import:RESISTOR_C0805")
      (libsource (lib "eagle-import") (part "RESISTOR0805"))
    )
    (comp (ref "C1")
      (value "10uF")
      (footprint "eagle-import:050_020_1")
      (libsource (lib "eagle-import") (part "0501"))
    )
    (comp (ref "C23")
      (value "100nF")
      (footprint "eagle-import:050X030_025")
      (libsource (lib "eagle-import") (part "CER/FILM1"))
    )
    (comp (ref "FSW1")
      (value "MOMENTARY")
      (footprint "eagle-import:SPST")
      (libsource (lib "eagle-import") (part "MOMENTARY"))
    )
    (comp (ref "FSW2")
      (value "MOMENTARY")
      (footprint "eagle-import:SPST")
      (libsource (lib "eagle-import") (part "MOMENTARY"))
    )
    (comp (ref "IC1")
      (value "PIC18F85J94")
      (footprint "eagle-import:TQFP80-12X12")
      (fields (field (name "MPN") "PIC18F85J50-I/PT"))
      (libsource (lib "eagle-import") (part "PIC18F8J505"))
    )
    (comp (ref "IC5")
      (value "24LC04B")
      (footprint "eagle-import:SOIC8")
      (libsource (lib "eagle-import") (part "24LC04B"))
    )
    (comp (ref "LOCK")
      (value "SPDTPIN_MOUNT")
      (footprint "eagle-import:1MS1T1B1C0M2QE")
      (libsource (lib "eagle-import") (part "SPDTPIN_MOUNT"))
    )
    (comp (ref "MODE")
      (value "SPDTPIN_MOUNT")
      (footprint "eagle-import:1MS1T1B1C0M2QE")
      (libsource (lib "eagle-import") (part "SPDTPIN_MOUNT"))
    )
    (comp (ref "PROG")
      (value "MA06-1")
      (footprint "eagle-import:MA06-1")
      (libsource (lib "eagle-import") (part "MA06-1"))
    )
    (comp (ref "R1")
      (value "10K")
      (footprint "eagle-import:RESISTOR_C0805")
      (libsource (lib "eagle-import") (part "RESISTOR0805"))
    )
    (comp (ref "R2")
      (value "470R")
      (footprint "eagle-import:RESISTOR_C0805")
      (libsource (lib "eagle-import") (part "RESISTOR0805"))
    )
    (comp (ref "R13")
      (value "10K")
      (footprint "eagle-import:RESISTOR_C0805")
      (fields (field (name "SPICEPREFIX") "R"))
      (libsource (lib "eagle-import") (part "RESISTOR0805"))
    )
    (comp (ref "R14")
      (value "10K")
      (footprint "eagle-import:RESISTOR_C0805")
      (fields (field (name "SPICEPREFIX") "R"))
      (libsource (lib "eagle-import") (part "RESISTOR0805"))
    )
    (comp (ref "R15")
      (value "10K")
      (footprint "eagle-import:RESISTOR_C0805")
      (fields (field (name "SPICEPREFIX") "R"))
      (libsource (lib "eagle-import") (part "RESISTOR0805"))
    )
    (comp (ref "R16")
      (value "10K")
      (footprint "eagle-import:RESISTOR_C0805")
      (fields (field (name "SPICEPREFIX") "R"))
      (libsource (lib "eagle-import") (part "RESISTOR0805"))
    )
    (comp (ref "R17")
      (value "10K")
      (footprint "eagle-import:RESISTOR_C0805")
      (fields (field (name "SPICEPREFIX") "R"))
      (libsource (lib "eagle-import") (part "RESISTOR0805"))
    )
    (comp (ref "R48")
      (value "10K")
      (footprint "eagle-import:RESISTOR_C0805")
      (fields (field (name "SPICEPREFIX") "R"))
      (libsource (lib "eagle-import") (part "RESISTOR0805"))
    )
    (comp (ref "R49")
      (value "10K")
      (footprint "eagle-import:RESISTOR_C0805")
      (fields (field (name "SPICEPREFIX") "R"))
      (libsource (lib "eagle-import") (part "RESISTOR0805"))
    )
    (comp (ref "R50")
      (value "10K")
      (footprint "eagle-import:RESISTOR_C0805")
      (fields (field (name "SPICEPREFIX") "R"))
      (libsource (lib "eagle-import") (part "RESISTOR0805"))
    )
    (comp (ref "R51")
      (value "10K")
      (footprint "eagle-import:RESISTOR_C0805")
      (fields (field (name "SPICEPREFIX") "R"))
      (libsource (lib "eagle-import") (part "RESISTOR0805"))
    )
    (comp (ref "R52")
      (value "10K")
      (footprint "eagle-import:RESISTOR_C0805")
      (fields (field (name "SPICEPREFIX") "R"))
      (libsource (lib "eagle-import") (part "RESISTOR0805"))
    )
    (comp (ref "S1")
      (value "MOMENTARY-SWITCH-SPST-PTH-6.0MM")
      (footprint "eagle-import:TACTILE_SWITCH_PTH_6.0MM")
      (fields (field (name "SPICEPREFIX") "B"))
      (libsource (lib "eagle-import") (part "MOMENTARY-SWITCH-SPST-PTH-6.0MM"))
    )
    (comp (ref "S2")
      (value "MOMENTARY-SWITCH-SPST-PTH-6.0MM")
      (footprint "eagle-import:TACTILE_SWITCH_PTH_6.0MM")
      (fields (field (name "SPICEPREFIX") "B"))
      (libsource (lib "eagle-import") (part "MOMENTARY-SWITCH-SPST-PTH-6.0MM"))
    )
    (comp (ref "S3")
      (value "MOMENTARY-SWITCH-SPST-PTH-6.0MM")
      (footprint "eagle-import:TACTILE_SWITCH_PTH_6.0MM")
      (fields (field (name "SPICEPREFIX") "B"))
      (libsource (lib "eagle-import") (part "MOMENTARY-SWITCH-SPST-PTH-6.0MM"))
    )
    (comp (ref "S4")
      (value "MOMENTARY-SWITCH-SPST-PTH-6.0MM")
      (footprint "eagle-import:TACTILE_SWITCH_PTH_6.0MM")
      (fields (field (name "SPICEPREFIX") "B"))
      (libsource (lib "eagle-import") (part "MOMENTARY-SWITCH-SPST-PTH-6.0MM"))
    )
    (comp (ref "S5")
      (value "MOMENTARY-SWITCH-SPST-PTH-6.0MM")
      (footprint "eagle-import:TACTILE_SWITCH_PTH_6.0MM")
      (fields (field (name "SPICEPREFIX") "B"))
      (libsource (lib "eagle-import") (part "MOMENTARY-SWITCH-SPST-PTH-6.0MM"))
    )
  )
  (nets
    (net (code "1") (name "CTRL") (class "Default")
      (node (ref "CTRL") (pin "1") (pinfunction "P_1") (pintype "passive"))
      (node (ref "CTRL1") (pin "1") (pinfunction "P_1") (pintype "passive"))
      (node (ref "IC1") (pin "67") (pinfunction "RD3/AD3/PMD3_67") (pintype "bidirectional"))
    )
    (net (code "2") (name "CV0") (class "Default")
      (node (ref "C20") (pin "1") (pinfunction "1_1") (pintype "passive"))
      (node (ref "IC1") (pin "30") (pinfunction "RA0/AN0_30") (pintype "bidirectional"))
      (node (ref "R10") (pin "2") (pinfunction "2_2") (pintype "passive"))
    )
    (net (code "3") (name "CV1") (class "Default")
      (node (ref "C18") (pin "1") (pinfunction "1_1") (pintype "passive"))
      (node (ref "IC1") (pin "29") (pinfunction "RA1/AN1_29") (pintype "bidirectional"))
      (node (ref "R8") (pin "2") (pinfunction "2_2") (pintype "passive"))
    )
    (net (code "4") (name "CV2") (class "Default")
      (node (ref "C16") (pin "1") (pinfunction "1_1") (pintype "passive"))
      (node (ref "IC1") (pin "28") (pinfunction "RA2/AN2/VREF-_28") (pintype "bidirectional"))
      (node (ref "R6") (pin "2") (pinfunction "2_2") (pintype "passive"))
    )
    (net (code "5") (name "CV3") (class "Default")
      (node (ref "C14") (pin "1") (pinfunction "1_1") (pintype "passive"))
      (node (ref "IC1") (pin "27") (pinfunction "RA3/AN3/VREF+_27") (pintype "bidirectional"))
      (node (ref "R4") (pin "2") (pinfunction "2_2") (pintype "passive"))
    )
    (net (code "6") (name "CV4") (class "Default")
      (node (ref "C21") (pin "1") (pinfunction "1_1") (pintype "passive"))
      (node (ref "IC1") (pin "33") (pinfunction "RA5/PMD4/AN4/C2INA_33") (pintype "bidirectional"))
      (node (ref "R11") (pin "2") (pinfunction "2_2") (pintype "passive"))
    )
    (net (code "7") (name "CV5") (class "Default")
      (node (ref "C19") (pin "1") (pinfunction "1_1") (pintype "passive"))
      (node (ref "IC1") (pin "13") (pinfunction "RF7/PMD0/~{SS1}/C1OUT_13") (pintype "bidirectional"))
      (node (ref "R9") (pin "2") (pinfunction "2_2") (pintype "passive"))
    )
    (net (code "8") (name "CV6") (class "Default")
      (node (ref "C15") (pin "1") (pinfunction "1_1") (pintype "passive"))
      (node (ref "IC1") (pin "34") (pinfunction "RA4/PMD5/T0CKI_34") (pintype "bidirectional"))
      (node (ref "R5") (pin "2") (pinfunction "2_2") (pintype "passive"))
    )
    (net (code "9") (name "CV7") (class "Default")
      (node (ref "C22") (pin "1") (pinfunction "1_1") (pintype "passive"))
      (node (ref "IC1") (pin "20") (pinfunction "RH6/PMRD/AN14/P1C/C1INC_20") (pintype "bidirectional"))
      (node (ref "R12") (pin "2") (pinfunction "2_2") (pintype "passive"))
    )
    (net (code "10") (name "CV8") (class "Default")
      (node (ref "C13") (pin "1") (pinfunction "1_1") (pintype "passive"))
      (node (ref "IC1") (pin "5") (pinfunction "RG0/PMA8/ECCP3/P3A_5") (pintype "bidirectional"))
      (node (ref "R3") (pin "2") (pinfunction "2_2") (pintype "passive"))
    )
    (net (code "11") (name "CV9") (class "Default")
      (node (ref "C17") (pin "1") (pinfunction "1_1") (pintype "passive"))
      (node (ref "IC1") (pin "43") (pinfunction "RC2/ECCP1/P1A_43") (pintype "bidirectional"))
      (node (ref "R7") (pin "2") (pinfunction "2_2") (pintype "passive"))
    )
    (net (code "12") (name "FSW1") (class "Default")
      (node (ref "FSW1") (pin "2") (pinfunction "S_2") (pintype "passive"))
      (node (ref "IC1") (pin "66") (pinfunction "RD4/AD4/PMD4/SDO2_66") (pintype "bidirectional"))
      (node (ref "R48") (pin "1") (pinfunction "1_1") (pintype "passive"))
    )
    (net (code "13") (name "FSW2") (class "Default")
      (node (ref "FSW2") (pin "2") (pinfunction "S_2") (pintype "passive"))
      (node (ref "IC1") (pin "77") (pinfunction "RE3/AD11/PMA13/P3C/REFO_77") (pintype "bidirectional"))
      (node (ref "R49") (pin "1") (pinfunction "1_1") (pintype "passive"))
    )
    (net (code "14") (name "INTA0") (class "Default")
      (node (ref "IC1") (pin "38") (pinfunction "RC7/RX1/DT1_38") (pintype "bidirectional"))
      (node (ref "IC2") (pin "9") (pinfunction "Q0_9") (pintype "output"))
    )
    (net (code "15") (name "INTA1") (class "Default")
      (node (ref "IC1") (pin "39") (pinfunction "RJ4/BA0_39") (pintype "bidirectional"))
      (node (ref "IC2") (pin "7") (pinfunction "Q1_7") (pintype "output"))
    )
    (net (code "16") (name "INTA2") (class "Default")
      (node (ref "IC1") (pin "40") (pinfunction "RJ5/~{CE}_40") (pintype "bidirectional"))
      (node (ref "IC2") (pin "6") (pinfunction "Q2_6") (pintype "output"))
    )
    (net (code "17") (name "INTB0") (class "Default")
      (node (ref "IC1") (pin "35") (pinfunction "RC1/T1OSI/ECCP2/P2A_35") (pintype "bidirectional"))
      (node (ref "IC3") (pin "9") (pinfunction "Q0_9") (pintype "output"))
    )
    (net (code "18") (name "INTB1") (class "Default")
      (node (ref "IC1") (pin "36") (pinfunction "RC0/T1OSO/T13CKI_36") (pintype "bidirectional"))
      (node (ref "IC3") (pin "7") (pinfunction "Q1_7") (pintype "output"))
    )
    (net (code "19") (name "INTB2") (class "Default")
      (node (ref "IC1") (pin "37") (pinfunction "RC6/TX1/CK1_37") (pintype "bidirectional"))
      (node (ref "IC3") (pin "6") (pinfunction "Q2_6") (pintype "output"))
    )
    (net (code "20") (name "INTC0") (class "Default")
      (node (ref "IC1") (pin "17") (pinfunction "RF3/D-_17") (pintype "bidirectional"))
      (node (ref "IC4") (pin "9") (pinfunction "Q0_9") (pintype "output"))
    )
    (net (code "21") (name "INTC1") (class "Default")
      (node (ref "IC1") (pin "21") (pinfunction "RH5/PMBE/AN13/P3B/C2IND_21") (pintype "bidirectional"))
      (node (ref "IC4") (pin "7") (pinfunction "Q1_7") (pintype "output"))
    )
    (net (code "22") (name "INTC2") (class "Default")
      (node (ref "IC1") (pin "22") (pinfunction "RH4/PMD3/AN12/P3C/C2INC_22") (pintype "bidirectional"))
      (node (ref "IC4") (pin "6") (pinfunction "Q2_6") (pintype "output"))
    )
    (net (code "23") (name "LED1") (class "Default")
      (node (ref "IC1") (pin "1") (pinfunction "RH2/A18/PMD7_1") (pintype "bidirectional"))
      (node (ref "R19") (pin "2") (pinfunction "2_2") (pintype "passive"))
    )
    (net (code "24") (name "LED2") (class "Default")
      (node (ref "IC1") (pin "76") (pinfunction "RE4/AD12/PMA12/P3B_76") (pintype "bidirectional"))
      (node (ref "R21") (pin "2") (pinfunction "2_2") (pintype "passive"))
    )
    (net (code "25") (name "LED3") (class "Default")
      (node (ref "IC1") (pin "75") (pinfunction "RE5/AD13/PMA11/P1C_75") (pintype "bidirectional"))
      (node (ref "R23") (pin "2") (pinfunction "2_2") (pintype "passive"))
    )
    (net (code "26") (name "LED4") (class "Default")
      (node (ref "IC1") (pin "73") (pinfunction "RE7/AD15/PMA9/ECCP2/P2A_73") (pintype "bidirectional"))
      (node (ref "R25") (pin "2") (pinfunction "2_2") (pintype "passive"))
    )
    (net (code "27") (name "LED5") (class "Default")
      (node (ref "IC1") (pin "72") (pinfunction "RD0/AD0/PMD0_72") (pintype "bidirectional"))
      (node (ref "R27") (pin "2") (pinfunction "2_2") (pintype "passive"))
    )
    (net (code "28") (name "LED6") (class "Default")
      (node (ref "IC1") (pin "68") (pinfunction "RD2/AD2/PMD2_68") (pintype "bidirectional"))
      (node (ref "R29") (pin "2") (pinfunction "2_2") (pintype "passive"))
    )
    (net (code "29") (name "LED7") (class "Default")
      (node (ref "IC1") (pin "4") (pinfunction "RE0/AD8/PMRD/P2D_4") (pintype "bidirectional"))
      (node (ref "R31") (pin "2") (pinfunction "2_2") (pintype "passive"))
    )
    (net (code "30") (name "LED8") (class "Default")
      (node (ref "IC1") (pin "79") (pinfunction "RH0/A16_79") (pintype "bidirectional"))
      (node (ref "R33") (pin "2") (pinfunction "2_2") (pintype "passive"))
    )
    (net (code "31") (name "LED9") (class "Default")
      (node (ref "IC1") (pin "10") (pinfunction "RG4/PMCS2/CCP5/P1D_10") (pintype "bidirectional"))
      (node (ref "R35") (pin "2") (pinfunction "2_2") (pintype "passive"))
    )
    (net (code "32") (name "LED10") (class "Default")
      (node (ref "IC1") (pin "19") (pinfunction "RH7/PMWR/AN15/P1B_19") (pintype "bidirectional"))
      (node (ref "R37") (pin "2") (pinfunction "2_2") (pintype "passive"))
    )
    (net (code "33") (name "LED11") (class "Default")
      (node (ref "IC1") (pin "18") (pinfunction "RF2/PMA5/AN7/C2INB_18") (pintype "bidirectional"))
      (node (ref "R39") (pin "2") (pinfunction "2_2") (pintype "passive"))
    )
    (net (code "34") (name "LED12") (class "Default")
      (node (ref "IC1") (pin "15") (pinfunction "RF5/PMD2/AN10/C1INB/CVREF_15") (pintype "bidirectional"))
      (node (ref "R41") (pin "2") (pinfunction "2_2") (pintype "passive"))
    )
    (net (code "35") (name "LED13") (class "Default")
      (node (ref "IC1") (pin "14") (pinfunction "RF6/PMD1/AN11/C1INA_14") (pintype "bidirectional"))
      (node (ref "R43") (pin "2") (pinfunction "2_2") (pintype "passive"))
    )
    (net (code "36") (name "LEDB") (class "Default")
      (node (ref "IC1") (pin "3") (pinfunction "RE1/AD9/PMWR/P2C_3") (pintype "bidirectional"))
      (node (ref "R47") (pin "1") (pinfunction "1_1") (pintype "passive"))
    )
    (net (code "37") (name "LEDR") (class "Default")
      (node (ref "IC1") (pin "80") (pinfunction "RH1/A17_80") (pintype "bidirectional"))
      (node (ref "R46") (pin "1") (pinfunction "1_1") (pintype "passive"))
    )
    (net (code "38") (name "LOCK") (class "Default")
      (node (ref "IC1") (pin "63") (pinfunction "RD7/AD7/PMD7/~{SS2}_63") (pintype "bidirectional"))
      (node (ref "LOCK") (pin "1") (pinfunction "O_1") (pintype "passive"))
      (node (ref "R52") (pin "1") (pinfunction "1_1") (pintype "passive"))
    )
    (net (code "39") (name "MODEA") (class "Default")
      (node (ref "IC1") (pin "61") (pinfunction "RJ1/~{OE}_61") (pintype "bidirectional"))
      (node (ref "MODE") (pin "1") (pinfunction "O_1") (pintype "passive"))
      (node (ref "R50") (pin "1") (pinfunction "1_1") (pintype "passive"))
    )
    (net (code "40") (name "MODEB") (class "Default")
      (node (ref "IC1") (pin "62") (pinfunction "RJ0/ALE_62") (pintype "bidirectional"))
      (node (ref "MODE") (pin "3") (pinfunction "S_3") (pintype "passive"))
      (node (ref "R51") (pin "1") (pinfunction "1_1") (pintype "passive"))
    )
    (net (code "41") (name "Net-(+9V-P)") (class "Default")
      (node (ref "+9V") (pin "1") (pinfunction "P_1") (pintype "passive"))
      (node (ref "C7") (pin "+") (pinfunction "+_+") (pintype "passive"))
      (node (ref "IC6") (pin "3") (pinfunction "IN_3") (pintype "bidirectional"))
      (node (ref "T2") (pin "2") (pinfunction "S_2") (pintype "passive"))
    )
    (net (code "42") (name "Net-(D1-PadA)") (class "Default")
      (node (ref "D1") (pin "A") (pinfunction "A_A") (pintype "passive"))
      (node (ref "R18") (pin "1") (pinfunction "1_1") (pintype "passive"))
    )
    (net (code "43") (name "Net-(D2-PadA)") (class "Default")
      (node (ref "D2") (pin "A") (pinfunction "A_A") (pintype "passive"))
      (node (ref "R20") (pin "1") (pinfunction "1_1") (pintype "passive"))
    )
    (net (code "44") (name "Net-(D3-PadA)") (class "Default")
      (node (ref "D3") (pin "A") (pinfunction "A_A") (pintype "passive"))
      (node (ref "R22") (pin "1") (pinfunction "1_1") (pintype "passive"))
    )
    (net (code "45") (name "Net-(D4-PadA)") (class "Default")
      (node (ref "D4") (pin "A") (pinfunction "A_A") (pintype "passive"))
      (node (ref "R24") (pin "1") (pinfunction "1_1") (pintype "passive"))
    )
    (net (code "46") (name "Net-(D5-PadA)") (class "Default")
      (node (ref "D5") (pin "A") (pinfunction "A_A") (pintype "passive"))
      (node (ref "R26") (pin "1") (pinfunction "1_1") (pintype "passive"))
    )
    (net (code "47") (name "Net-(D6-PadA)") (class "Default")
      (node (ref "D6") (pin "A") (pinfunction "A_A") (pintype "passive"))
      (node (ref "R28") (pin "1") (pinfunction "1_1") (pintype "passive"))
    )
    (net (code "48") (name "Net-(D7-PadA)") (class "Default")
      (node (ref "D7") (pin "A") (pinfunction "A_A") (pintype "passive"))
      (node (ref "R30") (pin "1") (pinfunction "1_1") (pintype "passive"))
    )
    (net (code "49") (name "Net-(D8-PadA)") (class "Default")
      (node (ref "D8") (pin "A") (pinfunction "A_A") (pintype "passive"))
      (node (ref "R32") (pin "1") (pinfunction "1_1") (pintype "passive"))
    )
    (net (code "50") (name "Net-(D9-PadA)") (class "Default")
      (node (ref "D9") (pin "A") (pinfunction "A_A") (pintype "passive"))
      (node (ref "R34") (pin "1") (pinfunction "1_1") (pintype "passive"))
    )
    (net (code "51") (name "Net-(D10-PadA)") (class "Default")
      (node (ref "D10") (pin "A") (pinfunction "A_A") (pintype "passive"))
      (node (ref "R36") (pin "1") (pinfunction "1_1") (pintype "passive"))
    )
    (net (code "52") (name "Net-(D11-PadA)") (class "Default")
      (node (ref "D11") (pin "A") (pinfunction "A_A") (pintype "passive"))
      (node (ref "R38") (pin "1") (pinfunction "1_1") (pintype "passive"))
    )
    (net (code "53") (name "Net-(D12-PadA)") (class "Default")
      (node (ref "D12") (pin "A") (pinfunction "A_A") (pintype "passive"))
      (node (ref "R40") (pin "1") (pinfunction "1_1") (pintype "passive"))
    )
    (net (code "54") (name "Net-(D13-PadA)") (class "Default")
      (node (ref "D13") (pin "A") (pinfunction "A_A") (pintype "passive"))
      (node (ref "R42") (pin "1") (pinfunction "1_1") (pintype "passive"))
    )
    (net (code "55") (name "Net-(D14-BLU-A)") (class "Default")
      (node (ref "D14") (pin "AB") (pinfunction "BLU-A_AB") (pintype "bidirectional"))
      (node (ref "R45") (pin "1") (pinfunction "1_1") (pintype "passive"))
    )
    (net (code "56") (name "Net-(D14-BLU-C)") (class "Default")
      (node (ref "D14") (pin "CB") (pinfunction "BLU-C_CB") (pintype "bidirectional"))
      (node (ref "Q15") (pin "3") (pinfunction "C_3") (pintype "passive"))
    )
    (net (code "57") (name "Net-(D14-RED-A)") (class "Default")
      (node (ref "D14") (pin "AR") (pinfunction "RED-A_AR") (pintype "bidirectional"))
      (node (ref "R44") (pin "1") (pinfunction "1_1") (pintype "passive"))
    )
    (net (code "58") (name "Net-(D14-RED-C)") (class "Default")
      (node (ref "D14") (pin "CR") (pinfunction "RED-C_CR") (pintype "bidirectional"))
      (node (ref "Q14") (pin "3") (pinfunction "C_3") (pintype "passive"))
    )
    (net (code "59") (name "Net-(DC1-PadR)") (class "Default")
      (node (ref "DC1") (pin "R") (pinfunction "R_R") (pintype "bidirectional"))
      (node (ref "DC1") (pin "S") (pinfunction "S_S") (pintype "bidirectional"))
      (node (ref "R80") (pin "2") (pinfunction "2_2") (pintype "passive"))
    )
    (net (code "60") (name "Net-(IC1-VDDCORE{slash}VCAP)") (class "Default")
      (node (ref "C1") (pin "+") (pinfunction "+_+") (pintype "passive"))
      (node (ref "IC1") (pin "12") (pinfunction "VDDCORE/VCAP_12") (pintype "bidirectional"))
    )
    (net (code "61") (name "Net-(IC1-~{MCLR})") (class "Default")
      (node (ref "IC1") (pin "9") (pinfunction "~{MCLR}_9") (pintype "input"))
      (node (ref "R2") (pin "1") (pinfunction "1_1") (pintype "passive"))
    )
    (net (code "62") (name "Net-(IC2A-D0)") (class "Default")
      (node (ref "IC2") (pin "10") (pinfunction "D0_10") (pintype "input"))
      (node (ref "R54") (pin "2") (pinfunction "2_2") (pintype "passive"))
      (node (ref "SW1") (pin "1") (pinfunction "1_1") (pintype "bidirectional"))
    )
    (net (code "63") (name "Net-(IC2A-D1)") (class "Default")
      (node (ref "IC2") (pin "11") (pinfunction "D1_11") (pintype "input"))
      (node (ref "R55") (pin "2") (pinfunction "2_2") (pintype "passive"))
      (node (ref "SW1") (pin "2") (pinfunction "2_2") (pintype "bidirectional"))
    )
    (net (code "64") (name "Net-(IC2A-D2)") (class "Default")
      (node (ref "IC2") (pin "12") (pinfunction "D2_12") (pintype "input"))
      (node (ref "R56") (pin "2") (pinfunction "2_2") (pintype "passive"))
      (node (ref "SW1") (pin "3") (pinfunction "3_3") (pintype "bidirectional"))
    )
    (net (code "65") (name "Net-(IC2A-D3)") (class "Default")
      (node (ref "IC2") (pin "13") (pinfunction "D3_13") (pintype "input"))
      (node (ref "R57") (pin "2") (pinfunction "2_2") (pintype "passive"))
      (node (ref "SW1") (pin "4") (pinfunction "4_4") (pintype "bidirectional"))
    )
    (net (code "66") (name "Net-(IC2A-D4)") (class "Default")
      (node (ref "IC2") (pin "1") (pinfunction "D4_1") (pintype "input"))
      (node (ref "R58") (pin "2") (pinfunction "2_2") (pintype "passive"))
      (node (ref "SW1") (pin "5") (pinfunction "5_5") (pintype "bidirectional"))
    )
    (net (code "67") (name "Net-(IC2A-D5)") (class "Default")
      (node (ref "IC2") (pin "2") (pinfunction "D5_2") (pintype "input"))
      (node (ref "R59") (pin "2") (pinfunction "2_2") (pintype "passive"))
      (node (ref "SW1") (pin "6") (pinfunction "6_6") (pintype "bidirectional"))
    )
    (net (code "68") (name "Net-(IC2A-D6)") (class "Default")
      (node (ref "IC2") (pin "3") (pinfunction "D6_3") (pintype "input"))
      (node (ref "R60") (pin "2") (pinfunction "2_2") (pintype "passive"))
      (node (ref "SW1") (pin "7") (pinfunction "7_7") (pintype "bidirectional"))
    )
    (net (code "69") (name "Net-(IC2A-D7)") (class "Default")
      (node (ref "IC2") (pin "4") (pinfunction "D7_4") (pintype "input"))
      (node (ref "R61") (pin "2") (pinfunction "2_2") (pintype "passive"))
      (node (ref "SW1") (pin "8") (pinfunction "8_8") (pintype "bidirectional"))
    )
    (net (code "70") (name "Net-(IC2A-EIN)") (class "Default")
      (node (ref "IC2") (pin "5") (pinfunction "EIN_5") (pintype "input"))
      (node (ref "R53") (pin "1") (pinfunction "1_1") (pintype "passive"))
    )
    (net (code "71") (name "Net-(IC3A-D0)") (class "Default")
      (node (ref "IC3") (pin "10") (pinfunction "D0_10") (pintype "input"))
      (node (ref "R63") (pin "2") (pinfunction "2_2") (pintype "passive"))
      (node (ref "SW2") (pin "1") (pinfunction "1_1") (pintype "bidirectional"))
    )
    (net (code "72") (name "Net-(IC3A-D1)") (class "Default")
      (node (ref "IC3") (pin "11") (pinfunction "D1_11") (pintype "input"))
      (node (ref "R64") (pin "2") (pinfunction "2_2") (pintype "passive"))
      (node (ref "SW2") (pin "2") (pinfunction "2_2") (pintype "bidirectional"))
    )
    (net (code "73") (name "Net-(IC3A-D2)") (class "Default")
      (node (ref "IC3") (pin "12") (pinfunction "D2_12") (pintype "input"))
      (node (ref "R65") (pin "2") (pinfunction "2_2") (pintype "passive"))
      (node (ref "SW2") (pin "3") (pinfunction "3_3") (pintype "bidirectional"))
    )
    (net (code "74") (name "Net-(IC3A-D3)") (class "Default")
      (node (ref "IC3") (pin "13") (pinfunction "D3_13") (pintype "input"))
      (node (ref "R66") (pin "2") (pinfunction "2_2") (pintype "passive"))
      (node (ref "SW2") (pin "4") (pinfunction "4_4") (pintype "bidirectional"))
    )
    (net (code "75") (name "Net-(IC3A-D4)") (class "Default")
      (node (ref "IC3") (pin "1") (pinfunction "D4_1") (pintype "input"))
      (node (ref "R67") (pin "2") (pinfunction "2_2") (pintype "passive"))
      (node (ref "SW2") (pin "5") (pinfunction "5_5") (pintype "bidirectional"))
    )
    (net (code "76") (name "Net-(IC3A-D5)") (class "Default")
      (node (ref "IC3") (pin "2") (pinfunction "D5_2") (pintype "input"))
      (node (ref "R68") (pin "2") (pinfunction "2_2") (pintype "passive"))
      (node (ref "SW2") (pin "6") (pinfunction "6_6") (pintype "bidirectional"))
    )
    (net (code "77") (name "Net-(IC3A-D6)") (class "Default")
      (node (ref "IC3") (pin "3") (pinfunction "D6_3") (pintype "input"))
      (node (ref "R69") (pin "2") (pinfunction "2_2") (pintype "passive"))
      (node (ref "SW2") (pin "7") (pinfunction "7_7") (pintype "bidirectional"))
    )
    (net (code "78") (name "Net-(IC3A-D7)") (class "Default")
      (node (ref "IC3") (pin "4") (pinfunction "D7_4") (pintype "input"))
      (node (ref "R70") (pin "2") (pinfunction "2_2") (pintype "passive"))
      (node (ref "SW2") (pin "8") (pinfunction "8_8") (pintype "bidirectional"))
    )
    (net (code "79") (name "Net-(IC3A-EIN)") (class "Default")
      (node (ref "IC3") (pin "5") (pinfunction "EIN_5") (pintype "input"))
      (node (ref "R62") (pin "1") (pinfunction "1_1") (pintype "passive"))
    )
    (net (code "80") (name "Net-(IC4A-D0)") (class "Default")
      (node (ref "IC4") (pin "10") (pinfunction "D0_10") (pintype "input"))
      (node (ref "R72") (pin "2") (pinfunction "2_2") (pintype "passive"))
      (node (ref "SW3") (pin "1") (pinfunction "1_1") (pintype "bidirectional"))
    )
    (net (code "81") (name "Net-(IC4A-D1)") (class "Default")
      (node (ref "IC4") (pin "11") (pinfunction "D1_11") (pintype "input"))
      (node (ref "R73") (pin "2") (pinfunction "2_2") (pintype "passive"))
      (node (ref "SW3") (pin "2") (pinfunction "2_2") (pintype "bidirectional"))
    )
    (net (code "82") (name "Net-(IC4A-D2)") (class "Default")
      (node (ref "IC4") (pin "12") (pinfunction "D2_12") (pintype "input"))
      (node (ref "R74") (pin "2") (pinfunction "2_2") (pintype "passive"))
      (node (ref "SW3") (pin "3") (pinfunction "3_3") (pintype "bidirectional"))
    )
    (net (code "83") (name "Net-(IC4A-D3)") (class "Default")
      (node (ref "IC4") (pin "13") (pinfunction "D3_13") (pintype "input"))
      (node (ref "R75") (pin "2") (pinfunction "2_2") (pintype "passive"))
      (node (ref "SW3") (pin "4") (pinfunction "4_4") (pintype "bidirectional"))
    )
    (net (code "84") (name "Net-(IC4A-D4)") (class "Default")
      (node (ref "IC4") (pin "1") (pinfunction "D4_1") (pintype "input"))
      (node (ref "R76") (pin "2") (pinfunction "2_2") (pintype "passive"))
      (node (ref "SW3") (pin "5") (pinfunction "5_5") (pintype "bidirectional"))
    )
    (net (code "85") (name "Net-(IC4A-D5)") (class "Default")
      (node (ref "IC4") (pin "2") (pinfunction "D5_2") (pintype "input"))
      (node (ref "R77") (pin "2") (pinfunction "2_2") (pintype "passive"))
      (node (ref "SW3") (pin "6") (pinfunction "6_6") (pintype "bidirectional"))
    )
    (net (code "86") (name "Net-(IC4A-D6)") (class "Default")
      (node (ref "IC4") (pin "3") (pinfunction "D6_3") (pintype "input"))
      (node (ref "R78") (pin "2") (pinfunction "2_2") (pintype "passive"))
      (node (ref "SW3") (pin "7") (pinfunction "7_7") (pintype "bidirectional"))
    )
    (net (code "87") (name "Net-(IC4A-D7)") (class "Default")
      (node (ref "IC4") (pin "4") (pinfunction "D7_4") (pintype "input"))
      (node (ref "R79") (pin "2") (pinfunction "2_2") (pintype "passive"))
      (node (ref "SW3") (pin "8") (pinfunction "8_8") (pintype "bidirectional"))
    )
    (net (code "88") (name "Net-(IC4A-EIN)") (class "Default")
      (node (ref "IC4") (pin "5") (pinfunction "EIN_5") (pintype "input"))
      (node (ref "R71") (pin "1") (pinfunction "1_1") (pintype "passive"))
    )
    (net (code "89") (name "Net-(POT0-2)") (class "Default")
      (node (ref "POT0") (pin "P$2") (pinfunction "2_P$2") (pintype "passive"))
      (node (ref "R3") (pin "1") (pinfunction "1_1") (pintype "passive"))
    )
    (net (code "90") (name "Net-(POT1-2)") (class "Default")
      (node (ref "POT1") (pin "P$2") (pinfunction "2_P$2") (pintype "passive"))
      (node (ref "R4") (pin "1") (pinfunction "1_1") (pintype "passive"))
    )
    (net (code "91") (name "Net-(POT2-2)") (class "Default")
      (node (ref "POT2") (pin "P$2") (pinfunction "2_P$2") (pintype "passive"))
      (node (ref "R5") (pin "1") (pinfunction "1_1") (pintype "passive"))
    )
    (net (code "92") (name "Net-(POT3-2)") (class "Default")
      (node (ref "POT3") (pin "P$2") (pinfunction "2_P$2") (pintype "passive"))
      (node (ref "R6") (pin "1") (pinfunction "1_1") (pintype "passive"))
    )
    (net (code "93") (name "Net-(POT4-2)") (class "Default")
      (node (ref "POT4") (pin "P$2") (pinfunction "2_P$2") (pintype "passive"))
      (node (ref "R7") (pin "1") (pinfunction "1_1") (pintype "passive"))
    )
    (net (code "94") (name "Net-(POT5-2)") (class "Default")
      (node (ref "POT5") (pin "P$2") (pinfunction "2_P$2") (pintype "passive"))
      (node (ref "R8") (pin "1") (pinfunction "1_1") (pintype "passive"))
    )
    (net (code "95") (name "Net-(POT6-2)") (class "Default")
      (node (ref "POT6") (pin "P$2") (pinfunction "2_P$2") (pintype "passive"))
      (node (ref "R9") (pin "1") (pinfunction "1_1") (pintype "passive"))
    )
    (net (code "96") (name "Net-(POT7-2)") (class "Default")
      (node (ref "POT7") (pin "P$2") (pinfunction "2_P$2") (pintype "passive"))
      (node (ref "R10") (pin "1") (pinfunction "1_1") (pintype "passive"))
    )
    (net (code "97") (name "Net-(POT8-2)") (class "Default")
      (node (ref "POT8") (pin "P$2") (pinfunction "2_P$2") (pintype "passive"))
      (node (ref "R11") (pin "1") (pinfunction "1_1") (pintype "passive"))
    )
    (net (code "98") (name "Net-(POT9-2)") (class "Default")
      (node (ref "POT9") (pin "P$2") (pinfunction "2_P$2") (pintype "passive"))
      (node (ref "R12") (pin "1") (pinfunction "1_1") (pintype "passive"))
    )
    (net (code "99") (name "Net-(Q1-B)") (class "Default")
      (node (ref "Q1") (pin "1") (pinfunction "B_1") (pintype "passive"))
      (node (ref "R19") (pin "1") (pinfunction "1_1") (pintype "passive"))
    )
    (net (code "100") (name "Net-(Q1-C)") (class "Default")
      (node (ref "D1") (pin "C") (pinfunction "C_C") (pintype "passive"))
      (node (ref "Q1") (pin "3") (pinfunction "C_3") (pintype "passive"))
    )
    (net (code "101") (name "Net-(Q2-B)") (class "Default")
      (node (ref "Q2") (pin "1") (pinfunction "B_1") (pintype "passive"))
      (node (ref "R21") (pin "1") (pinfunction "1_1") (pintype "passive"))
    )
    (net (code "102") (name "Net-(Q2-C)") (class "Default")
      (node (ref "D2") (pin "C") (pinfunction "C_C") (pintype "passive"))
      (node (ref "Q2") (pin "3") (pinfunction "C_3") (pintype "passive"))
    )
    (net (code "103") (name "Net-(Q3-B)") (class "Default")
      (node (ref "Q3") (pin "1") (pinfunction "B_1") (pintype "passive"))
      (node (ref "R23") (pin "1") (pinfunction "1_1") (pintype "passive"))
    )
    (net (code "104") (name "Net-(Q3-C)") (class "Default")
      (node (ref "D3") (pin "C") (pinfunction "C_C") (pintype "passive"))
      (node (ref "Q3") (pin "3") (pinfunction "C_3") (pintype "passive"))
    )
    (net (code "105") (name "Net-(Q4-B)") (class "Default")
      (node (ref "Q4") (pin "1") (pinfunction "B_1") (pintype "passive"))
      (node (ref "R25") (pin "1") (pinfunction "1_1") (pintype "passive"))
    )
    (net (code "106") (name "Net-(Q4-C)") (class "Default")
      (node (ref "D4") (pin "C") (pinfunction "C_C") (pintype "passive"))
      (node (ref "Q4") (pin "3") (pinfunction "C_3") (pintype "passive"))
    )
    (net (code "107") (name "Net-(Q5-B)") (class "Default")
      (node (ref "Q5") (pin "1") (pinfunction "B_1") (pintype "passive"))
      (node (ref "R27") (pin "1") (pinfunction "1_1") (pintype "passive"))
    )
    (net (code "108") (name "Net-(Q5-C)") (class "Default")
      (node (ref "D5") (pin "C") (pinfunction "C_C") (pintype "passive"))
      (node (ref "Q5") (pin "3") (pinfunction "C_3") (pintype "passive"))
    )
    (net (code "109") (name "Net-(Q6-B)") (class "Default")
      (node (ref "Q6") (pin "1") (pinfunction "B_1") (pintype "passive"))
      (node (ref "R29") (pin "1") (pinfunction "1_1") (pintype "passive"))
    )
    (net (code "110") (name "Net-(Q6-C)") (class "Default")
      (node (ref "D6") (pin "C") (pinfunction "C_C") (pintype "passive"))
      (node (ref "Q6") (pin "3") (pinfunction "C_3") (pintype "passive"))
    )
    (net (code "111") (name "Net-(Q7-B)") (class "Default")
      (node (ref "Q7") (pin "1") (pinfunction "B_1") (pintype "passive"))
      (node (ref "R31") (pin "1") (pinfunction "1_1") (pintype "passive"))
    )
    (net (code "112") (name "Net-(Q7-C)") (class "Default")
      (node (ref "D7") (pin "C") (pinfunction "C_C") (pintype "passive"))
      (node (ref "Q7") (pin "3") (pinfunction "C_3") (pintype "passive"))
    )
    (net (code "113") (name "Net-(Q8-B)") (class "Default")
      (node (ref "Q8") (pin "1") (pinfunction "B_1") (pintype "passive"))
      (node (ref "R33") (pin "1") (pinfunction "1_1") (pintype "passive"))
    )
    (net (code "114") (name "Net-(Q8-C)") (class "Default")
      (node (ref "D8") (pin "C") (pinfunction "C_C") (pintype "passive"))
      (node (ref "Q8") (pin "3") (pinfunction "C_3") (pintype "passive"))
    )
    (net (code "115") (name "Net-(Q9-B)") (class "Default")
      (node (ref "Q9") (pin "1") (pinfunction "B_1") (pintype "passive"))
      (node (ref "R35") (pin "1") (pinfunction "1_1") (pintype "passive"))
    )
    (net (code "116") (name "Net-(Q9-C)") (class "Default")
      (node (ref "D9") (pin "C") (pinfunction "C_C") (pintype "passive"))
      (node (ref "Q9") (pin "3") (pinfunction "C_3") (pintype "passive"))
    )
    (net (code "117") (name "Net-(Q10-B)") (class "Default")
      (node (ref "Q10") (pin "1") (pinfunction "B_1") (pintype "passive"))
      (node (ref "R37") (pin "1") (pinfunction "1_1") (pintype "passive"))
    )
    (net (code "118") (name "Net-(Q10-C)") (class "Default")
      (node (ref "D10") (pin "C") (pinfunction "C_C") (pintype "passive"))
      (node (ref "Q10") (pin "3") (pinfunction "C_3") (pintype "passive"))
    )
    (net (code "119") (name "Net-(Q11-B)") (class "Default")
      (node (ref "Q11") (pin "1") (pinfunction "B_1") (pintype "passive"))
      (node (ref "R39") (pin "1") (pinfunction "1_1") (pintype "passive"))
    )
    (net (code "120") (name "Net-(Q11-C)") (class "Default")
      (node (ref "D11") (pin "C") (pinfunction "C_C") (pintype "passive"))
      (node (ref "Q11") (pin "3") (pinfunction "C_3") (pintype "passive"))
    )
    (net (code "121") (name "Net-(Q12-B)") (class "Default")
      (node (ref "Q12") (pin "1") (pinfunction "B_1") (pintype "passive"))
      (node (ref "R41") (pin "1") (pinfunction "1_1") (pintype "passive"))
    )
    (net (code "122") (name "Net-(Q12-C)") (class "Default")
      (node (ref "D12") (pin "C") (pinfunction "C_C") (pintype "passive"))
      (node (ref "Q12") (pin "3") (pinfunction "C_3") (pintype "passive"))
    )
    (net (code "123") (name "Net-(Q13-B)") (class "Default")
      (node (ref "Q13") (pin "1") (pinfunction "B_1") (pintype "passive"))
      (node (ref "R43") (pin "1") (pinfunction "1_1") (pintype "passive"))
    )
    (net (code "124") (name "Net-(Q13-C)") (class "Default")
      (node (ref "D13") (pin "C") (pinfunction "C_C") (pintype "passive"))
      (node (ref "Q13") (pin "3") (pinfunction "C_3") (pintype "passive"))
    )
    (net (code "125") (name "Net-(Q14-B)") (class "Default")
      (node (ref "Q14") (pin "1") (pinfunction "B_1") (pintype "passive"))
      (node (ref "R46") (pin "2") (pinfunction "2_2") (pintype "passive"))
    )
    (net (code "126") (name "Net-(Q15-B)") (class "Default")
      (node (ref "Q15") (pin "1") (pinfunction "B_1") (pintype "passive"))
      (node (ref "R47") (pin "2") (pinfunction "2_2") (pintype "passive"))
    )
    (net (code "127") (name "Net-(T2-D)") (class "Default")
      (node (ref "C9") (pin "+") (pinfunction "+_+") (pintype "passive"))
      (node (ref "R80") (pin "1") (pinfunction "1_1") (pintype "passive"))
      (node (ref "T2") (pin "1") (pinfunction "D_1") (pintype "passive"))
    )
    (net (code "128") (name "PGC") (class "Default")
      (node (ref "IC1") (pin "52") (pinfunction "RB6/KBI2/PGC_52") (pintype "bidirectional"))
      (node (ref "PROG") (pin "5") (pinfunction "5_5") (pintype "passive"))
    )
    (net (code "129") (name "PGD") (class "Default")
      (node (ref "IC1") (pin "47") (pinfunction "RB7/KBI3/PGD_47") (pintype "bidirectional"))
      (node (ref "PROG") (pin "4") (pinfunction "4_4") (pintype "passive"))
    )
    (net (code "130") (name "SCL1") (class "Default")
      (node (ref "IC1") (pin "44") (pinfunction "RC3/SCK1/SCL1_44") (pintype "bidirectional"))
      (node (ref "IC5") (pin "6") (pinfunction "SCL_6") (pintype "bidirectional"))
      (node (ref "R81") (pin "1") (pinfunction "1_1") (pintype "passive"))
      (node (ref "SCL1") (pin "1") (pinfunction "P_1") (pintype "passive"))
    )
    (net (code "131") (name "SCL2") (class "Default")
      (node (ref "IC1") (pin "64") (pinfunction "RD6/AD6/PMD6/SCK2/SCL2_64") (pintype "bidirectional"))
      (node (ref "SCL2") (pin "1") (pinfunction "P_1") (pintype "passive"))
    )
    (net (code "132") (name "SDA1") (class "Default")
      (node (ref "IC1") (pin "45") (pinfunction "RC4/SDI1/SDA1_45") (pintype "bidirectional"))
      (node (ref "IC5") (pin "5") (pinfunction "SDA_5") (pintype "bidirectional"))
      (node (ref "R82") (pin "1") (pinfunction "1_1") (pintype "passive"))
      (node (ref "SDA1") (pin "1") (pinfunction "P_1") (pintype "passive"))
    )
    (net (code "133") (name "SDA2") (class "Default")
      (node (ref "IC1") (pin "65") (pinfunction "RD5/AD5/PMD5/SDI2/SDA2_65") (pintype "bidirectional"))
      (node (ref "SDA2") (pin "1") (pinfunction "P_1") (pintype "passive"))
    )
    (net (code "134") (name "SW1") (class "Default")
      (node (ref "IC1") (pin "6") (pinfunction "RG1/PMA7/TX2/CK2_6") (pintype "bidirectional"))
      (node (ref "R13") (pin "1") (pinfunction "1_1") (pintype "passive"))
      (node (ref "S1") (pin "3") (pinfunction "2_3") (pintype "passive"))
    )
    (net (code "135") (name "SW2") (class "Default")
      (node (ref "IC1") (pin "7") (pinfunction "RG2/PMA6/RX2/DT2_7") (pintype "bidirectional"))
      (node (ref "R14") (pin "1") (pinfunction "1_1") (pintype "passive"))
      (node (ref "S2") (pin "3") (pinfunction "2_3") (pintype "passive"))
    )
    (net (code "136") (name "SW3") (class "Default")
      (node (ref "IC1") (pin "74") (pinfunction "RE6/AD14/PMA10/P1B_74") (pintype "bidirectional"))
      (node (ref "R15") (pin "1") (pinfunction "1_1") (pintype "passive"))
      (node (ref "S3") (pin "3") (pinfunction "2_3") (pintype "passive"))
    )
    (net (code "137") (name "SW4") (class "Default")
      (node (ref "IC1") (pin "69") (pinfunction "RD1/AD1/PMD1_69") (pintype "bidirectional"))
      (node (ref "R16") (pin "1") (pinfunction "1_1") (pintype "passive"))
      (node (ref "S4") (pin "3") (pinfunction "2_3") (pintype "passive"))
    )
    (net (code "138") (name "SW5") (class "Default")
      (node (ref "IC1") (pin "8") (pinfunction "RG3/PMCS1/CCP4/P3D_8") (pintype "bidirectional"))
      (node (ref "R17") (pin "1") (pinfunction "1_1") (pintype "passive"))
      (node (ref "S5") (pin "3") (pinfunction "2_3") (pintype "passive"))
    )
    (net (code "139") (name "TAILS") (class "Default")
      (node (ref "IC1") (pin "53") (pinfunction "RB5/KBI1/PMA0_53") (pintype "bidirectional"))
      (node (ref "TAILS") (pin "1") (pinfunction "P_1") (pintype "passive"))
    )
    (net (code "140") (name "VDD") (class "Default")
      (node (ref "C10") (pin "2") (pinfunction "2_2") (pintype "passive"))
      (node (ref "C11") (pin "2") (pinfunction "2_2") (pintype "passive"))
      (node (ref "C12") (pin "2") (pinfunction "2_2") (pintype "passive"))
      (node (ref "C2") (pin "1") (pinfunction "1_1") (pintype "passive"))
      (node (ref "C23") (pin "1") (pinfunction "1_1") (pintype "passive"))
      (node (ref "C3") (pin "1") (pinfunction "1_1") (pintype "passive"))
      (node (ref "C4") (pin "1") (pinfunction "1_1") (pintype "passive"))
      (node (ref "C5") (pin "1") (pinfunction "1_1") (pintype "passive"))
      (node (ref "C6") (pin "+") (pinfunction "+_+") (pintype "passive"))
      (node (ref "C8") (pin "1") (pinfunction "1_1") (pintype "passive"))
      (node (ref "IC1") (pin "23") (pinfunction "VUSB_23") (pintype "input"))
      (node (ref "IC1") (pin "25") (pinfunction "AVDD_25") (pintype "bidirectional"))
      (node (ref "IC1") (pin "32") (pinfunction "VDD_32") (pintype "power_in"))
      (node (ref "IC1") (pin "48") (pinfunction "VDD_48") (pintype "power_in"))
      (node (ref "IC1") (pin "71") (pinfunction "VDD_71") (pintype "power_in"))
      (node (ref "IC5") (pin "8") (pinfunction "VCC_8") (pintype "bidirectional"))
      (node (ref "IC6") (pin "2") (pinfunction "OUT_2") (pintype "bidirectional"))
      (node (ref "POT0") (pin "P$3") (pinfunction "3_P$3") (pintype "passive"))
      (node (ref "POT1") (pin "P$3") (pinfunction "3_P$3") (pintype "passive"))
      (node (ref "POT2") (pin "P$3") (pinfunction "3_P$3") (pintype "passive"))
      (node (ref "POT3") (pin "P$3") (pinfunction "3_P$3") (pintype "passive"))
      (node (ref "POT4") (pin "P$3") (pinfunction "3_P$3") (pintype "passive"))
      (node (ref "POT5") (pin "P$3") (pinfunction "3_P$3") (pintype "passive"))
      (node (ref "POT6") (pin "P$3") (pinfunction "3_P$3") (pintype "passive"))
      (node (ref "POT7") (pin "P$3") (pinfunction "3_P$3") (pintype "passive"))
      (node (ref "POT8") (pin "P$3") (pinfunction "3_P$3") (pintype "passive"))
      (node (ref "POT9") (pin "P$3") (pinfunction "3_P$3") (pintype "passive"))
      (node (ref "PROG") (pin "2") (pinfunction "2_2") (pintype "passive"))
      (node (ref "R1") (pin "2") (pinfunction "2_2") (pintype "passive"))
      (node (ref "R13") (pin "2") (pinfunction "2_2") (pintype "passive"))
      (node (ref "R14") (pin "2") (pinfunction "2_2") (pintype "passive"))
      (node (ref "R15") (pin "2") (pinfunction "2_2") (pintype "passive"))
      (node (ref "R16") (pin "2") (pinfunction "2_2") (pintype "passive"))
      (node (ref "R17") (pin "2") (pinfunction "2_2") (pintype "passive"))
      (node (ref "R18") (pin "2") (pinfunction "2_2") (pintype "passive"))
      (node (ref "R20") (pin "2") (pinfunction "2_2") (pintype "passive"))
      (node (ref "R22") (pin "2") (pinfunction "2_2") (pintype "passive"))
      (node (ref "R24") (pin "2") (pinfunction "2_2") (pintype "passive"))
      (node (ref "R26") (pin "2") (pinfunction "2_2") (pintype "passive"))
      (node (ref "R28") (pin "2") (pinfunction "2_2") (pintype "passive"))
      (node (ref "R30") (pin "2") (pinfunction "2_2") (pintype "passive"))
      (node (ref "R32") (pin "2") (pinfunction "2_2") (pintype "passive"))
      (node (ref "R34") (pin "2") (pinfunction "2_2") (pintype "passive"))
      (node (ref "R36") (pin "2") (pinfunction "2_2") (pintype "passive"))
      (node (ref "R38") (pin "2") (pinfunction "2_2") (pintype "passive"))
      (node (ref "R40") (pin "2") (pinfunction "2_2") (pintype "passive"))
      (node (ref "R42") (pin "2") (pinfunction "2_2") (pintype "passive"))
      (node (ref "R44") (pin "2") (pinfunction "2_2") (pintype "passive"))
      (node (ref "R45") (pin "2") (pinfunction "2_2") (pintype "passive"))
      (node (ref "R48") (pin "2") (pinfunction "2_2") (pintype "passive"))
      (node (ref "R49") (pin "2") (pinfunction "2_2") (pintype "passive"))
      (node (ref "R50") (pin "2") (pinfunction "2_2") (pintype "passive"))
      (node (ref "R51") (pin "2") (pinfunction "2_2") (pintype "passive"))
      (node (ref "R52") (pin "2") (pinfunction "2_2") (pintype "passive"))
      (node (ref "R53") (pin "2") (pinfunction "2_2") (pintype "passive"))
      (node (ref "R62") (pin "2") (pinfunction "2_2") (pintype "passive"))
      (node (ref "R71") (pin "2") (pinfunction "2_2") (pintype "passive"))
      (node (ref "R81") (pin "2") (pinfunction "2_2") (pintype "passive"))
      (node (ref "R82") (pin "2") (pinfunction "2_2") (pintype "passive"))
      (node (ref "SW1") (pin "C") (pinfunction "A_C") (pintype "bidirectional"))
      (node (ref "SW2") (pin "C") (pinfunction "A_C") (pintype "bidirectional"))
      (node (ref "SW3") (pin "C") (pinfunction "A_C") (pintype "bidirectional"))
    )
    (net (code "141") (name "VSS") (class "Default")
      (node (ref "C1") (pin "-") (pinfunction "-_-") (pintype "passive"))
      (node (ref "C10") (pin "1") (pinfunction "1_1") (pintype "passive"))
      (node (ref "C11") (pin "1") (pinfunction "1_1") (pintype "passive"))
      (node (ref "C12") (pin "1") (pinfunction "1_1") (pintype "passive"))
      (node (ref "C13") (pin "2") (pinfunction "2_2") (pintype "passive"))
      (node (ref "C14") (pin "2") (pinfunction "2_2") (pintype "passive"))
      (node (ref "C15") (pin "2") (pinfunction "2_2") (pintype "passive"))
      (node (ref "C16") (pin "2") (pinfunction "2_2") (pintype "passive"))
      (node (ref "C17") (pin "2") (pinfunction "2_2") (pintype "passive"))
      (node (ref "C18") (pin "2") (pinfunction "2_2") (pintype "passive"))
      (node (ref "C19") (pin "2") (pinfunction "2_2") (pintype "passive"))
      (node (ref "C2") (pin "2") (pinfunction "2_2") (pintype "passive"))
      (node (ref "C20") (pin "2") (pinfunction "2_2") (pintype "passive"))
      (node (ref "C21") (pin "2") (pinfunction "2_2") (pintype "passive"))
      (node (ref "C22") (pin "2") (pinfunction "2_2") (pintype "passive"))
      (node (ref "C23") (pin "2") (pinfunction "2_2") (pintype "passive"))
      (node (ref "C3") (pin "2") (pinfunction "2_2") (pintype "passive"))
      (node (ref "C4") (pin "2") (pinfunction "2_2") (pintype "passive"))
      (node (ref "C5") (pin "2") (pinfunction "2_2") (pintype "passive"))
      (node (ref "C6") (pin "-") (pinfunction "-_-") (pintype "passive"))
      (node (ref "C7") (pin "-") (pinfunction "-_-") (pintype "passive"))
      (node (ref "C8") (pin "2") (pinfunction "2_2") (pintype "passive"))
      (node (ref "C9") (pin "-") (pinfunction "-_-") (pintype "passive"))
      (node (ref "DC1") (pin "T") (pinfunction "T_T") (pintype "bidirectional"))
      (node (ref "FSW1") (pin "1") (pinfunction "P_1") (pintype "passive"))
      (node (ref "FSW2") (pin "1") (pinfunction "P_1") (pintype "passive"))
      (node (ref "GND") (pin "1") (pinfunction "P_1") (pintype "passive"))
      (node (ref "IC1") (pin "11") (pinfunction "VSS_11") (pintype "power_in"))
      (node (ref "IC1") (pin "26") (pinfunction "AVSS_26") (pintype "bidirectional"))
      (node (ref "IC1") (pin "31") (pinfunction "VSS_31") (pintype "power_in"))
      (node (ref "IC1") (pin "51") (pinfunction "VSS_51") (pintype "power_in"))
      (node (ref "IC1") (pin "70") (pinfunction "VSS_70") (pintype "power_in"))
      (node (ref "IC5") (pin "4") (pinfunction "VSS_4") (pintype "bidirectional"))
      (node (ref "IC5") (pin "7") (pinfunction "WP_7") (pintype "bidirectional"))
      (node (ref "IC6") (pin "1") (pinfunction "GND_1") (pintype "bidirectional"))
      (node (ref "LOCK") (pin "2") (pinfunction "P_2") (pintype "passive"))
      (node (ref "MODE") (pin "2") (pinfunction "P_2") (pintype "passive"))
      (node (ref "POT0") (pin "P$1") (pinfunction "1_P$1") (pintype "passive"))
      (node (ref "POT1") (pin "P$1") (pinfunction "1_P$1") (pintype "passive"))
      (node (ref "POT2") (pin "P$1") (pinfunction "1_P$1") (pintype "passive"))
      (node (ref "POT3") (pin "P$1") (pinfunction "1_P$1") (pintype "passive"))
      (node (ref "POT4") (pin "P$1") (pinfunction "1_P$1") (pintype "passive"))
      (node (ref "POT5") (pin "P$1") (pinfunction "1_P$1") (pintype "passive"))
      (node (ref "POT6") (pin "P$1") (pinfunction "1_P$1") (pintype "passive"))
      (node (ref "POT7") (pin "P$1") (pinfunction "1_P$1") (pintype "passive"))
      (node (ref "POT8") (pin "P$1") (pinfunction "1_P$1") (pintype "passive"))
      (node (ref "POT9") (pin "P$1") (pinfunction "1_P$1") (pintype "passive"))
      (node (ref "PROG") (pin "3") (pinfunction "3_3") (pintype "passive"))
      (node (ref "Q1") (pin "2") (pinfunction "E_2") (pintype "passive"))
      (node (ref "Q10") (pin "2") (pinfunction "E_2") (pintype "passive"))
      (node (ref "Q11") (pin "2") (pinfunction "E_2") (pintype "passive"))
      (node (ref "Q12") (pin "2") (pinfunction "E_2") (pintype "passive"))
      (node (ref "Q13") (pin "2") (pinfunction "E_2") (pintype "passive"))
      (node (ref "Q14") (pin "2") (pinfunction "E_2") (pintype "passive"))
      (node (ref "Q15") (pin "2") (pinfunction "E_2") (pintype "passive"))
      (node (ref "Q2") (pin "2") (pinfunction "E_2") (pintype "passive"))
      (node (ref "Q3") (pin "2") (pinfunction "E_2") (pintype "passive"))
      (node (ref "Q4") (pin "2") (pinfunction "E_2") (pintype "passive"))
      (node (ref "Q5") (pin "2") (pinfunction "E_2") (pintype "passive"))
      (node (ref "Q6") (pin "2") (pinfunction "E_2") (pintype "passive"))
      (node (ref "Q7") (pin "2") (pinfunction "E_2") (pintype "passive"))
      (node (ref "Q8") (pin "2") (pinfunction "E_2") (pintype "passive"))
      (node (ref "Q9") (pin "2") (pinfunction "E_2") (pintype "passive"))
      (node (ref "R54") (pin "1") (pinfunction "1_1") (pintype "passive"))
      (node (ref "R55") (pin "1") (pinfunction "1_1") (pintype "passive"))
      (node (ref "R56") (pin "1") (pinfunction "1_1") (pintype "passive"))
      (node (ref "R57") (pin "1") (pinfunction "1_1") (pintype "passive"))
      (node (ref "R58") (pin "1") (pinfunction "1_1") (pintype "passive"))
      (node (ref "R59") (pin "1") (pinfunction "1_1") (pintype "passive"))
      (node (ref "R60") (pin "1") (pinfunction "1_1") (pintype "passive"))
      (node (ref "R61") (pin "1") (pinfunction "1_1") (pintype "passive"))
      (node (ref "R63") (pin "1") (pinfunction "1_1") (pintype "passive"))
      (node (ref "R64") (pin "1") (pinfunction "1_1") (pintype "passive"))
      (node (ref "R65") (pin "1") (pinfunction "1_1") (pintype "passive"))
      (node (ref "R66") (pin "1") (pinfunction "1_1") (pintype "passive"))
      (node (ref "R67") (pin "1") (pinfunction "1_1") (pintype "passive"))
      (node (ref "R68") (pin "1") (pinfunction "1_1") (pintype "passive"))
      (node (ref "R69") (pin "1") (pinfunction "1_1") (pintype "passive"))
      (node (ref "R70") (pin "1") (pinfunction "1_1") (pintype "passive"))
      (node (ref "R72") (pin "1") (pinfunction "1_1") (pintype "passive"))
      (node (ref "R73") (pin "1") (pinfunction "1_1") (pintype "passive"))
      (node (ref "R74") (pin "1") (pinfunction "1_1") (pintype "passive"))
      (node (ref "R75") (pin "1") (pinfunction "1_1") (pintype "passive"))
      (node (ref "R76") (pin "1") (pinfunction "1_1") (pintype "passive"))
      (node (ref "R77") (pin "1") (pinfunction "1_1") (pintype "passive"))
      (node (ref "R78") (pin "1") (pinfunction "1_1") (pintype "passive"))
      (node (ref "R79") (pin "1") (pinfunction "1_1") (pintype "passive"))
      (node (ref "S1") (pin "1") (pinfunction "1_1") (pintype "passive"))
      (node (ref "S2") (pin "1") (pinfunction "1_1") (pintype "passive"))
      (node (ref "S3") (pin "1") (pinfunction "1_1") (pintype "passive"))
      (node (ref "S4") (pin "1") (pinfunction "1_1") (pintype "passive"))
      (node (ref "S5") (pin "1") (pinfunction "1_1") (pintype "passive"))
      (node (ref "SPR1") (pin "P$1") (pinfunction "P$1_P$1") (pintype "bidirectional"))
      (node (ref "SPR1") (pin "P$2") (pinfunction "P$2_P$2") (pintype "bidirectional"))
      (node (ref "SPR1") (pin "P$3") (pinfunction "P$3_P$3") (pintype "bidirectional"))
      (node (ref "T2") (pin "3") (pinfunction "G_3") (pintype "passive"))
    )
    (net (code "142") (name "unconnected-(D14-GRN-A-PadAG)") (class "Default")
      (node (ref "D14") (pin "AG") (pinfunction "GRN-A_AG") (pintype "bidirectional"))
    )
    (net (code "143") (name "unconnected-(D14-GRN-C-PadCG)") (class "Default")
      (node (ref "D14") (pin "CG") (pinfunction "GRN-C_CG") (pintype "bidirectional"))
    )
    (net (code "144") (name "unconnected-(IC1-ENVREG-Pad24)") (class "Default")
      (node (ref "IC1") (pin "24") (pinfunction "ENVREG_24") (pintype "input"))
    )
    (net (code "145") (name "unconnected-(IC1-OSC1{slash}CLKI{slash}RA7-Pad49)") (class "Default")
      (node (ref "IC1") (pin "49") (pinfunction "OSC1/CLKI/RA7_49") (pintype "bidirectional"))
    )
    (net (code "146") (name "unconnected-(IC1-OSC2{slash}CLKO{slash}RA6-Pad50)") (class "Default")
      (node (ref "IC1") (pin "50") (pinfunction "OSC2/CLKO/RA6_50") (pintype "bidirectional"))
    )
    (net (code "147") (name "unconnected-(IC1-RB0{slash}FLT0{slash}INT0-Pad58)") (class "Default")
      (node (ref "IC1") (pin "58") (pinfunction "RB0/FLT0/INT0_58") (pintype "bidirectional"))
    )
    (net (code "148") (name "unconnected-(IC1-RB1{slash}INT1{slash}PMA4-Pad57)") (class "Default")
      (node (ref "IC1") (pin "57") (pinfunction "RB1/INT1/PMA4_57") (pintype "bidirectional"))
    )
    (net (code "149") (name "unconnected-(IC1-RB2{slash}INT2{slash}PMA3-Pad56)") (class "Default")
      (node (ref "IC1") (pin "56") (pinfunction "RB2/INT2/PMA3_56") (pintype "bidirectional"))
    )
    (net (code "150") (name "unconnected-(IC1-RB3{slash}INT3{slash}ECCP2{slash}P2A{slash}PMA2-Pad55)") (class "Default")
      (node (ref "IC1") (pin "55") (pinfunction "RB3/INT3/ECCP2/P2A/PMA2_55") (pintype "bidirectional"))
    )
    (net (code "151") (name "unconnected-(IC1-RB4{slash}KBI0{slash}PMA1-Pad54)") (class "Default")
      (node (ref "IC1") (pin "54") (pinfunction "RB4/KBI0/PMA1_54") (pintype "bidirectional"))
    )
    (net (code "152") (name "unconnected-(IC1-RC5{slash}SDO1{slash}C2OUT-Pad46)") (class "Default")
      (node (ref "IC1") (pin "46") (pinfunction "RC5/SDO1/C2OUT_46") (pintype "bidirectional"))
    )
    (net (code "153") (name "unconnected-(IC1-RE2{slash}AD10{slash}PMBE{slash}P2B-Pad78)") (class "Default")
      (node (ref "IC1") (pin "78") (pinfunction "RE2/AD10/PMBE/P2B_78") (pintype "bidirectional"))
    )
    (net (code "154") (name "unconnected-(IC1-RF4{slash}D+-Pad16)") (class "Default")
      (node (ref "IC1") (pin "16") (pinfunction "RF4/D+_16") (pintype "bidirectional"))
    )
    (net (code "155") (name "unconnected-(IC1-RH3{slash}A19{slash}PMD6-Pad2)") (class "Default")
      (node (ref "IC1") (pin "2") (pinfunction "RH3/A19/PMD6_2") (pintype "bidirectional"))
    )
    (net (code "156") (name "unconnected-(IC1-RJ2{slash}~{WRL}-Pad60)") (class "Default")
      (node (ref "IC1") (pin "60") (pinfunction "RJ2/~{WRL}_60") (pintype "bidirectional"))
    )
    (net (code "157") (name "unconnected-(IC1-RJ3{slash}~{WRH}-Pad59)") (class "Default")
      (node (ref "IC1") (pin "59") (pinfunction "RJ3/~{WRH}_59") (pintype "bidirectional"))
    )
    (net (code "158") (name "unconnected-(IC1-RJ6{slash}~{LB}-Pad41)") (class "Default")
      (node (ref "IC1") (pin "41") (pinfunction "RJ6/~{LB}_41") (pintype "bidirectional"))
    )
    (net (code "159") (name "unconnected-(IC1-RJ7{slash}~{UB}-Pad42)") (class "Default")
      (node (ref "IC1") (pin "42") (pinfunction "RJ7/~{UB}_42") (pintype "bidirectional"))
    )
    (net (code "160") (name "unconnected-(IC2A-EOUT-Pad15)") (class "Default")
      (node (ref "IC2") (pin "15") (pinfunction "EOUT_15") (pintype "output"))
    )
    (net (code "161") (name "unconnected-(IC2A-GS-Pad14)") (class "Default")
      (node (ref "IC2") (pin "14") (pinfunction "GS_14") (pintype "output"))
    )
    (net (code "162") (name "unconnected-(IC3A-EOUT-Pad15)") (class "Default")
      (node (ref "IC3") (pin "15") (pinfunction "EOUT_15") (pintype "output"))
    )
    (net (code "163") (name "unconnected-(IC3A-GS-Pad14)") (class "Default")
      (node (ref "IC3") (pin "14") (pinfunction "GS_14") (pintype "output"))
    )
    (net (code "164") (name "unconnected-(IC4A-EOUT-Pad15)") (class "Default")
      (node (ref "IC4") (pin "15") (pinfunction "EOUT_15") (pintype "output"))
    )
    (net (code "165") (name "unconnected-(IC4A-GS-Pad14)") (class "Default")
      (node (ref "IC4") (pin "14") (pinfunction "GS_14") (pintype "output"))
    )
    (net (code "166") (name "unconnected-(IC5-A0-Pad1)") (class "Default")
      (node (ref "IC5") (pin "1") (pinfunction "A0_1") (pintype "bidirectional"))
    )
    (net (code "167") (name "unconnected-(IC5-A1-Pad2)") (class "Default")
      (node (ref "IC5") (pin "2") (pinfunction "A1_2") (pintype "bidirectional"))
    )
    (net (code "168") (name "unconnected-(IC5-A2-Pad3)") (class "Default")
      (node (ref "IC5") (pin "3") (pinfunction "A2_3") (pintype "bidirectional"))
    )
    (net (code "169") (name "unconnected-(LOCK-S-Pad3)") (class "Default")
      (node (ref "LOCK") (pin "3") (pinfunction "S_3") (pintype "passive"))
    )
    (net (code "170") (name "unconnected-(PROG-Pad6)") (class "Default")
      (node (ref "PROG") (pin "6") (pinfunction "6_6") (pintype "passive"))
    )
    (net (code "171") (name "unconnected-(X-P-Pad1)") (class "Default")
      (node (ref "X") (pin "1") (pinfunction "P_1") (pintype "passive"))
    )
    (net (code "172") (name "~{MCLR}") (class "Default")
      (node (ref "PROG") (pin "1") (pinfunction "1_1") (pintype "passive"))
      (node (ref "R1") (pin "1") (pinfunction "1_1") (pintype "passive"))
      (node (ref "R2") (pin "2") (pinfunction "2_2") (pintype "passive"))
    )
  )
)
